# aircat.net
KiCad netlist of a schematic drawn in EAGLE
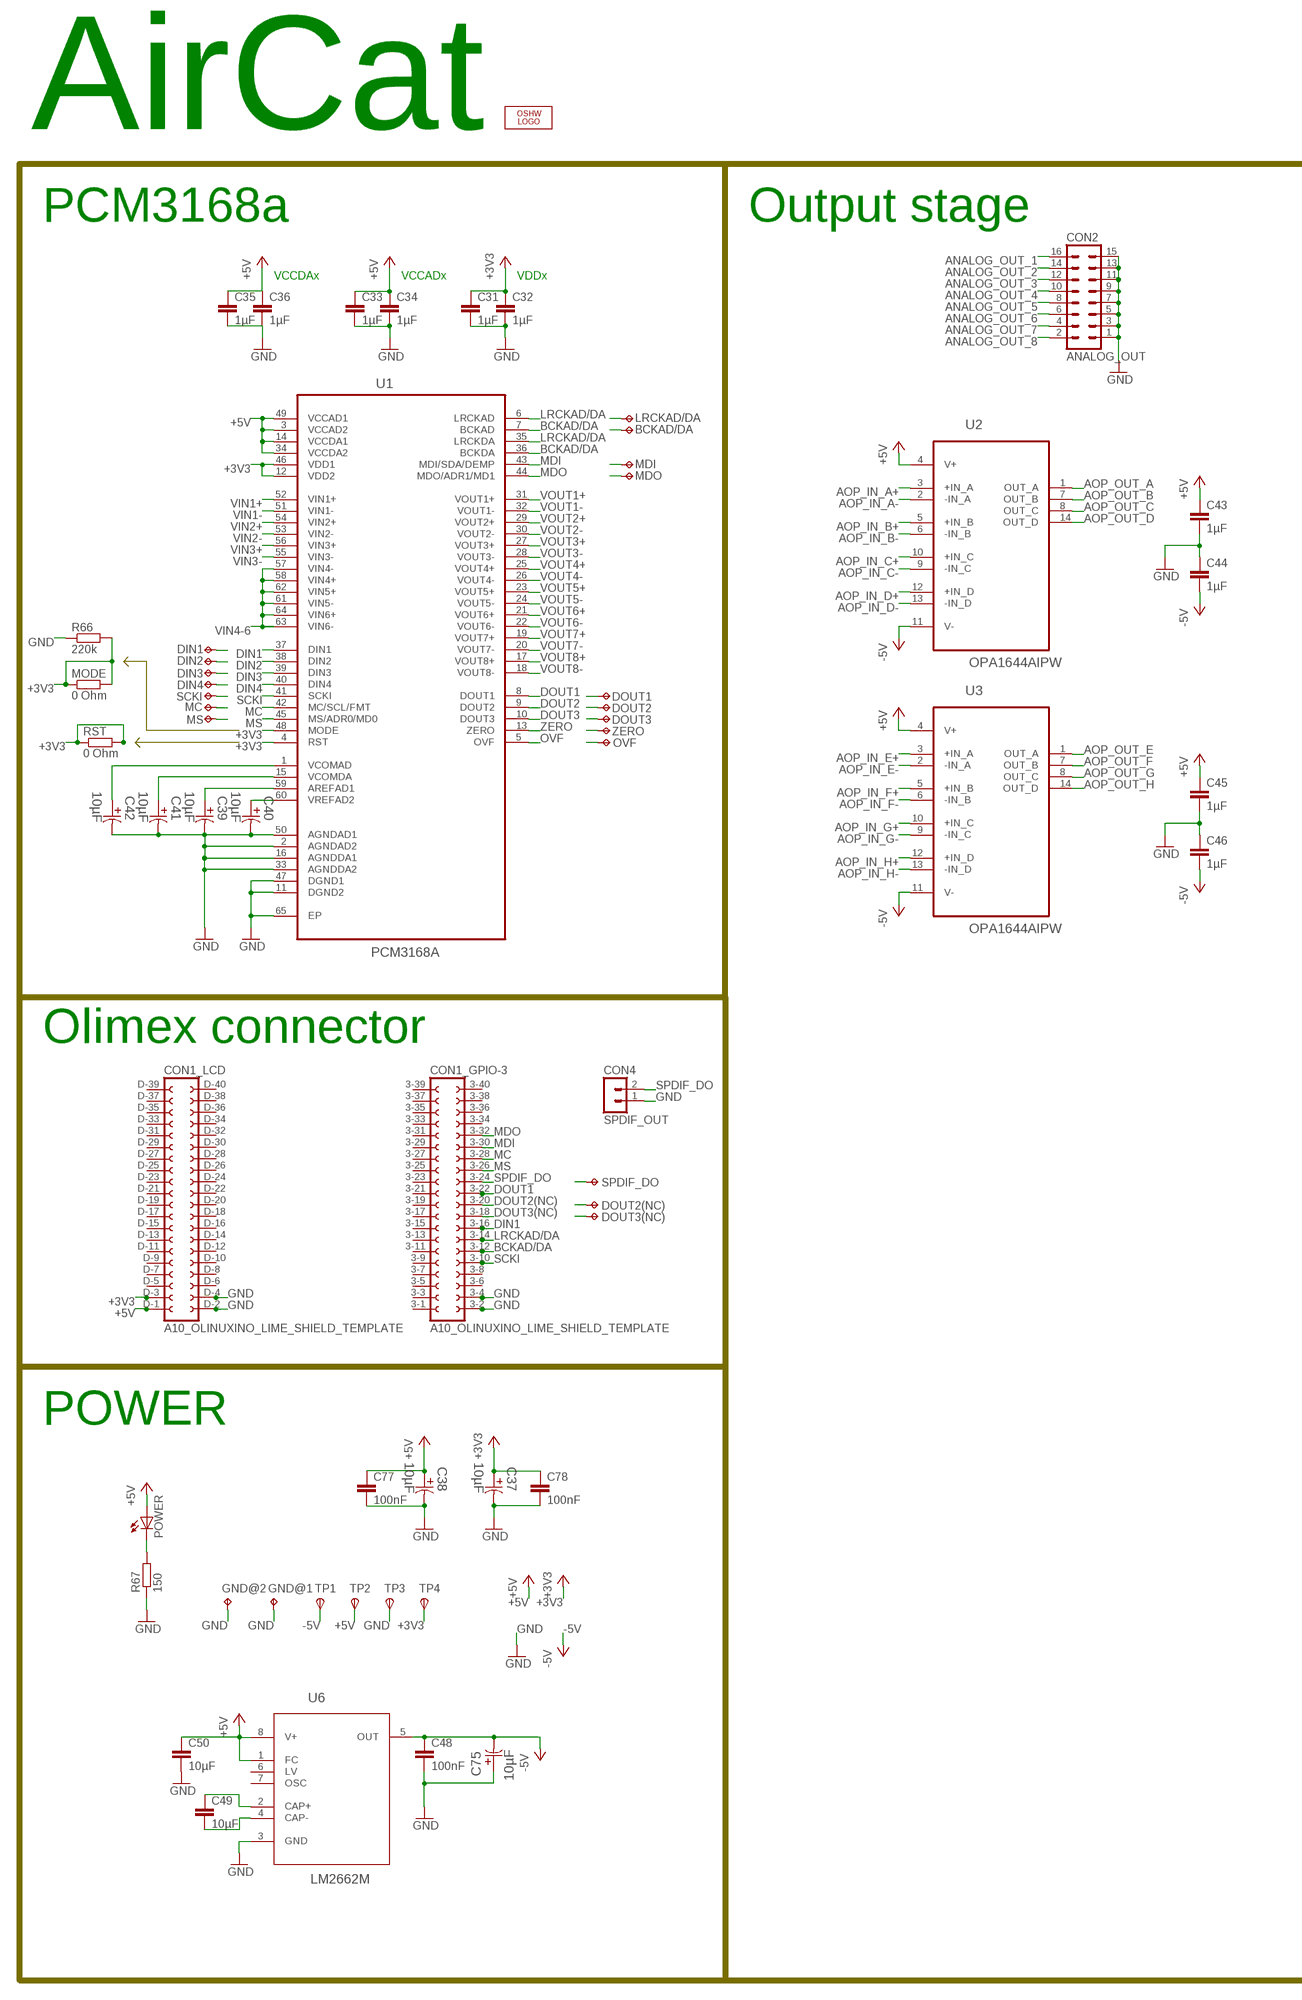
[diagram p0: schematic, sheet 1, part 1 of 2]
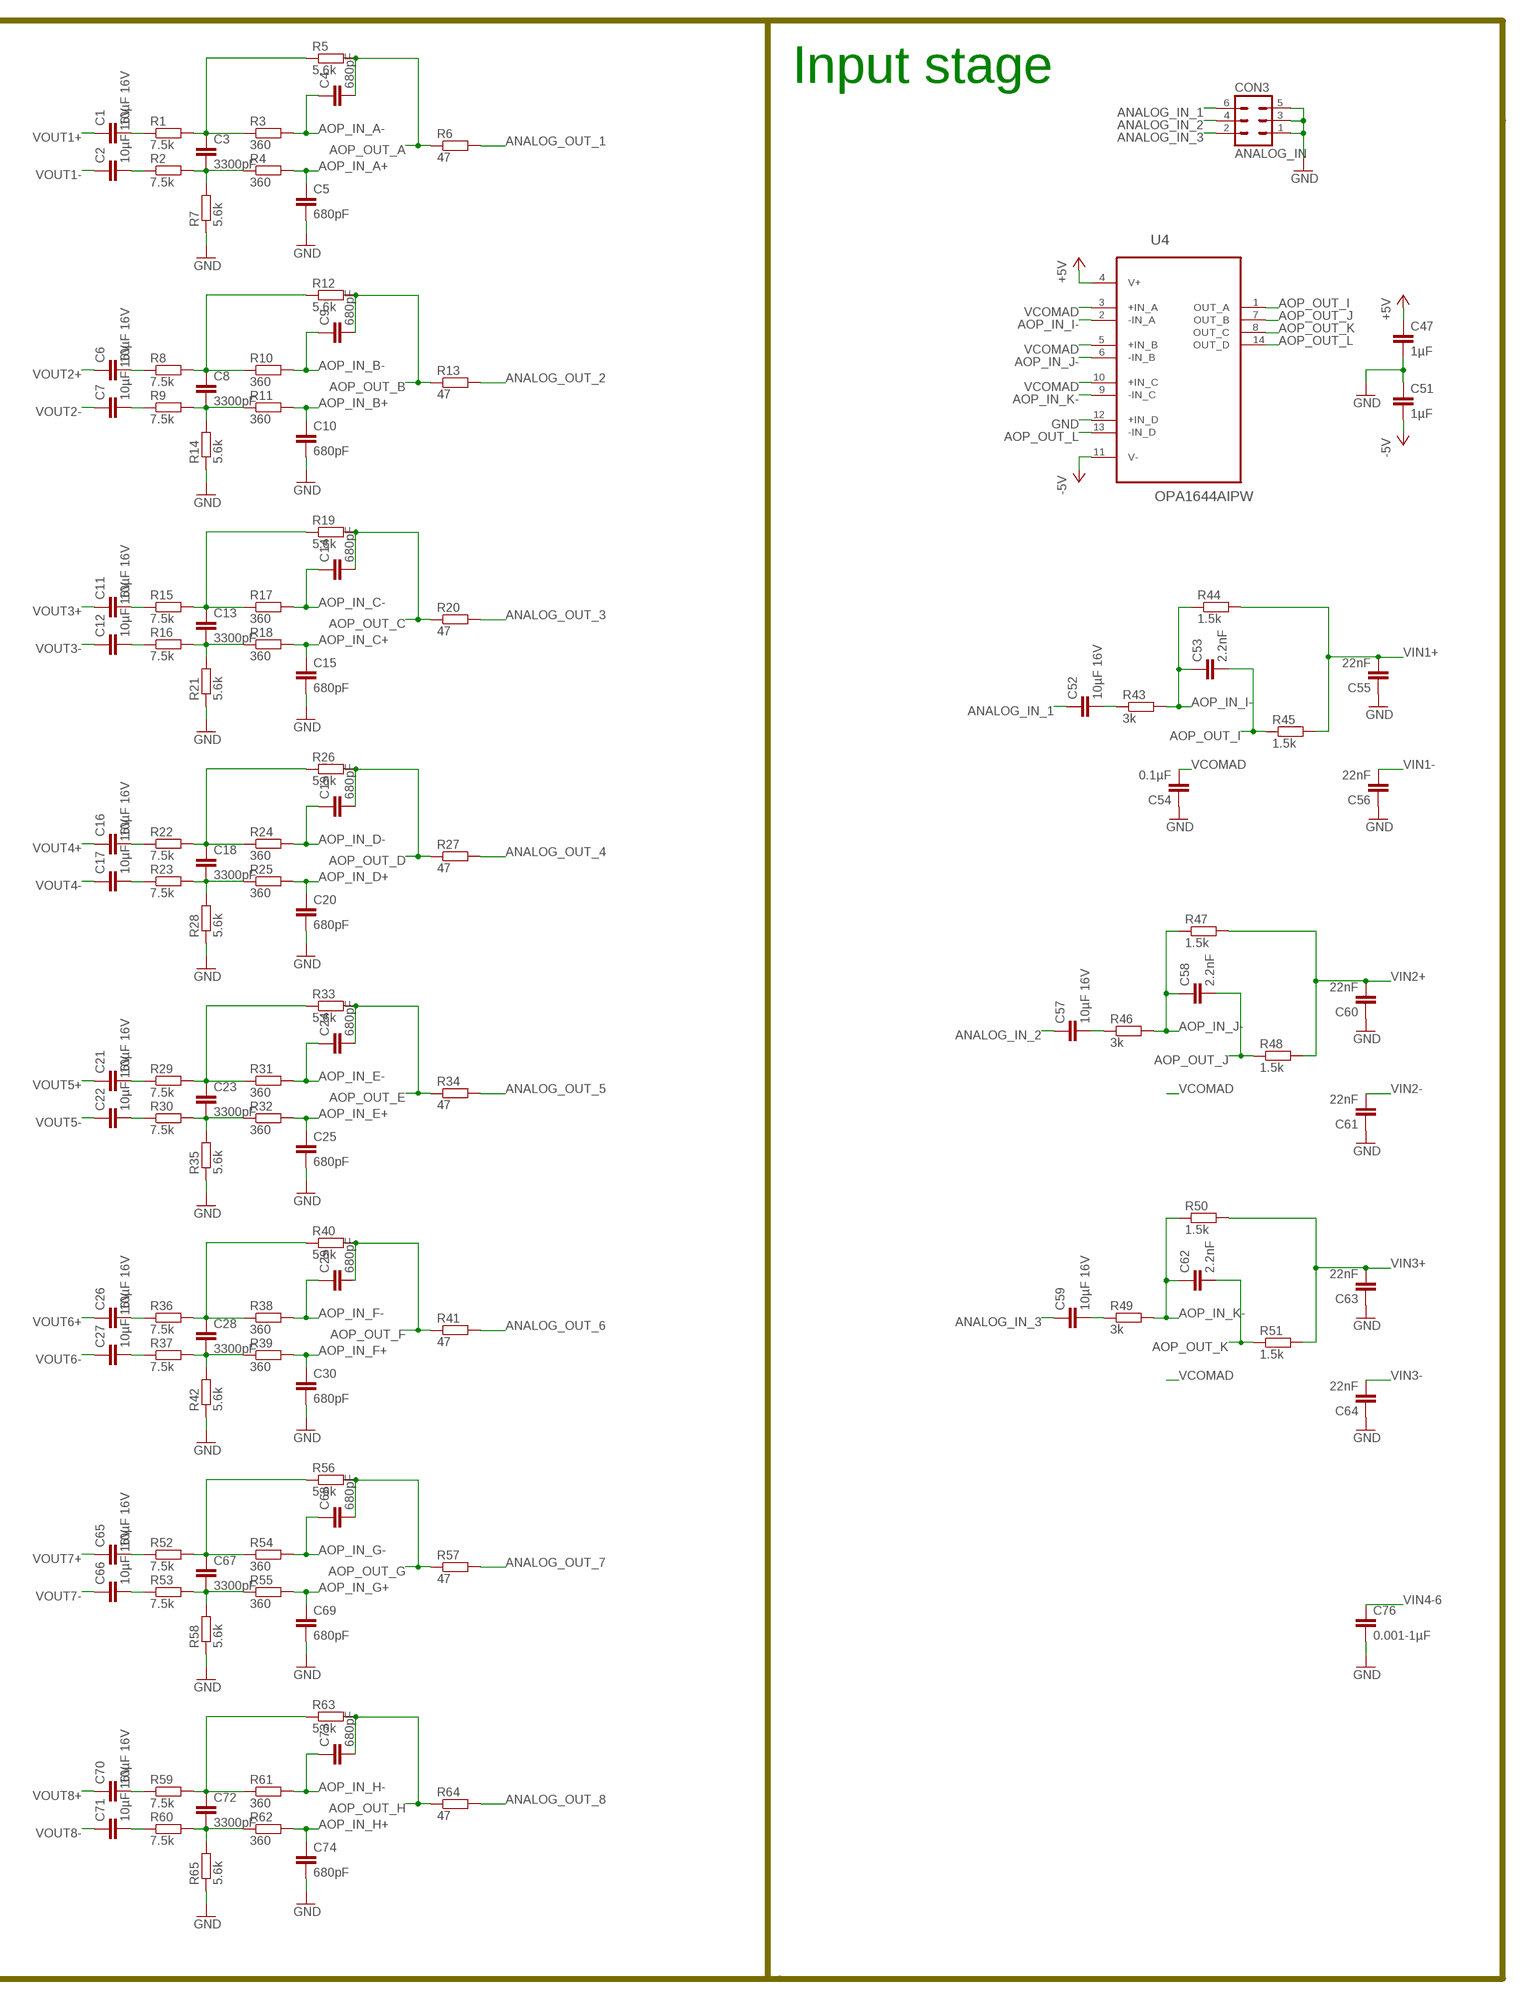
[diagram p1: schematic, sheet 1, part 2 of 2]

(export (version "E")
  (design (tool "Eeschema 10.0.6"))
  (components
    (comp (ref "BCKAD/DA")
      (value "TPTP10SQ")
      (footprint "eagle-import:TP10SQ")
      (libsource (lib "eagle-import") (part "TPTP10SQ"))
    )
    (comp (ref "C1")
      (value "10µF 16V")
      (footprint "eagle-import:C0805")
      (fields (field (name "MF") "AVX") (field (name "MPN") "1206YD106KAT2A"))
      (libsource (lib "eagle-import") (part "C-EUC0805"))
    )
    (comp (ref "C2")
      (value "10µF 16V")
      (footprint "eagle-import:C0805")
      (fields (field (name "MF") "AVX") (field (name "MPN") "1206YD106KAT2A"))
      (libsource (lib "eagle-import") (part "C-EUC0805"))
    )
    (comp (ref "C3")
      (value "3300pF")
      (footprint "eagle-import:C0603")
      (fields (field (name "MF") "AVX") (field (name "MPN") "06035C332KAT2A"))
      (libsource (lib "eagle-import") (part "C-EUC0603"))
    )
    (comp (ref "C4")
      (value "680pF")
      (footprint "eagle-import:C0603")
      (fields (field (name "MF") "KEMET") (field (name "MPN") "C0603C681J5GACTU"))
      (libsource (lib "eagle-import") (part "C-EUC0603"))
    )
    (comp (ref "C5")
      (value "680pF")
      (footprint "eagle-import:C0603")
      (fields (field (name "MF") "KEMET") (field (name "MPN") "C0603C681J5GACTU"))
      (libsource (lib "eagle-import") (part "C-EUC0603"))
    )
    (comp (ref "C6")
      (value "10µF 16V")
      (footprint "eagle-import:C0805")
      (fields (field (name "MF") "AVX") (field (name "MPN") "1206YD106KAT2A"))
      (libsource (lib "eagle-import") (part "C-EUC0805"))
    )
    (comp (ref "C7")
      (value "10µF 16V")
      (footprint "eagle-import:C0805")
      (fields (field (name "MF") "AVX") (field (name "MPN") "1206YD106KAT2A"))
      (libsource (lib "eagle-import") (part "C-EUC0805"))
    )
    (comp (ref "C8")
      (value "3300pF")
      (footprint "eagle-import:C0603")
      (fields (field (name "MF") "AVX") (field (name "MPN") "06035C332KAT2A"))
      (libsource (lib "eagle-import") (part "C-EUC0603"))
    )
    (comp (ref "C9")
      (value "680pF")
      (footprint "eagle-import:C0603")
      (fields (field (name "MF") "KEMET") (field (name "MPN") "C0603C681J5GACTU"))
      (libsource (lib "eagle-import") (part "C-EUC0603"))
    )
    (comp (ref "C10")
      (value "680pF")
      (footprint "eagle-import:C0603")
      (fields (field (name "MF") "KEMET") (field (name "MPN") "C0603C681J5GACTU"))
      (libsource (lib "eagle-import") (part "C-EUC0603"))
    )
    (comp (ref "C11")
      (value "10µF 16V")
      (footprint "eagle-import:C0805")
      (fields (field (name "MF") "AVX") (field (name "MPN") "1206YD106KAT2A"))
      (libsource (lib "eagle-import") (part "C-EUC0805"))
    )
    (comp (ref "C12")
      (value "10µF 16V")
      (footprint "eagle-import:C0805")
      (fields (field (name "MF") "AVX") (field (name "MPN") "1206YD106KAT2A"))
      (libsource (lib "eagle-import") (part "C-EUC0805"))
    )
    (comp (ref "C13")
      (value "3300pF")
      (footprint "eagle-import:C0603")
      (fields (field (name "MF") "AVX") (field (name "MPN") "06035C332KAT2A"))
      (libsource (lib "eagle-import") (part "C-EUC0603"))
    )
    (comp (ref "C14")
      (value "680pF")
      (footprint "eagle-import:C0603")
      (fields (field (name "MF") "KEMET") (field (name "MPN") "C0603C681J5GACTU"))
      (libsource (lib "eagle-import") (part "C-EUC0603"))
    )
    (comp (ref "C15")
      (value "680pF")
      (footprint "eagle-import:C0603")
      (fields (field (name "MF") "KEMET") (field (name "MPN") "C0603C681J5GACTU"))
      (libsource (lib "eagle-import") (part "C-EUC0603"))
    )
    (comp (ref "C16")
      (value "10µF 16V")
      (footprint "eagle-import:C0805")
      (fields (field (name "MF") "AVX") (field (name "MPN") "1206YD106KAT2A"))
      (libsource (lib "eagle-import") (part "C-EUC0805"))
    )
    (comp (ref "C17")
      (value "10µF 16V")
      (footprint "eagle-import:C0805")
      (fields (field (name "MF") "AVX") (field (name "MPN") "1206YD106KAT2A"))
      (libsource (lib "eagle-import") (part "C-EUC0805"))
    )
    (comp (ref "C18")
      (value "3300pF")
      (footprint "eagle-import:C0603")
      (fields (field (name "MF") "AVX") (field (name "MPN") "06035C332KAT2A"))
      (libsource (lib "eagle-import") (part "C-EUC0603"))
    )
    (comp (ref "C19")
      (value "680pF")
      (footprint "eagle-import:C0603")
      (fields (field (name "MF") "KEMET") (field (name "MPN") "C0603C681J5GACTU"))
      (libsource (lib "eagle-import") (part "C-EUC0603"))
    )
    (comp (ref "C20")
      (value "680pF")
      (footprint "eagle-import:C0603")
      (fields (field (name "MF") "KEMET") (field (name "MPN") "C0603C681J5GACTU"))
      (libsource (lib "eagle-import") (part "C-EUC0603"))
    )
    (comp (ref "C21")
      (value "10µF 16V")
      (footprint "eagle-import:C0805")
      (fields (field (name "MF") "AVX") (field (name "MPN") "1206YD106KAT2A"))
      (libsource (lib "eagle-import") (part "C-EUC0805"))
    )
    (comp (ref "C22")
      (value "10µF 16V")
      (footprint "eagle-import:C0805")
      (fields (field (name "MF") "AVX") (field (name "MPN") "1206YD106KAT2A"))
      (libsource (lib "eagle-import") (part "C-EUC0805"))
    )
    (comp (ref "C23")
      (value "3300pF")
      (footprint "eagle-import:C0603")
      (fields (field (name "MF") "AVX") (field (name "MPN") "06035C332KAT2A"))
      (libsource (lib "eagle-import") (part "C-EUC0603"))
    )
    (comp (ref "C24")
      (value "680pF")
      (footprint "eagle-import:C0603")
      (fields (field (name "MF") "KEMET") (field (name "MPN") "C0603C681J5GACTU"))
      (libsource (lib "eagle-import") (part "C-EUC0603"))
    )
    (comp (ref "C25")
      (value "680pF")
      (footprint "eagle-import:C0603")
      (fields (field (name "MF") "KEMET") (field (name "MPN") "C0603C681J5GACTU"))
      (libsource (lib "eagle-import") (part "C-EUC0603"))
    )
    (comp (ref "C26")
      (value "10µF 16V")
      (footprint "eagle-import:C0805")
      (fields (field (name "MF") "AVX") (field (name "MPN") "1206YD106KAT2A"))
      (libsource (lib "eagle-import") (part "C-EUC0805"))
    )
    (comp (ref "C27")
      (value "10µF 16V")
      (footprint "eagle-import:C0805")
      (fields (field (name "MF") "AVX") (field (name "MPN") "1206YD106KAT2A"))
      (libsource (lib "eagle-import") (part "C-EUC0805"))
    )
    (comp (ref "C28")
      (value "3300pF")
      (footprint "eagle-import:C0603")
      (fields (field (name "MF") "AVX") (field (name "MPN") "06035C332KAT2A"))
      (libsource (lib "eagle-import") (part "C-EUC0603"))
    )
    (comp (ref "C29")
      (value "680pF")
      (footprint "eagle-import:C0603")
      (fields (field (name "MF") "KEMET") (field (name "MPN") "C0603C681J5GACTU"))
      (libsource (lib "eagle-import") (part "C-EUC0603"))
    )
    (comp (ref "C30")
      (value "680pF")
      (footprint "eagle-import:C0603")
      (fields (field (name "MF") "KEMET") (field (name "MPN") "C0603C681J5GACTU"))
      (libsource (lib "eagle-import") (part "C-EUC0603"))
    )
    (comp (ref "C31")
      (value "1µF")
      (footprint "eagle-import:C0603")
      (fields (field (name "MF") "AVX") (field (name "MPN") "0603ZD105KAT2A"))
      (libsource (lib "eagle-import") (part "C-EUC0603"))
    )
    (comp (ref "C32")
      (value "1µF")
      (footprint "eagle-import:C0603")
      (fields (field (name "MF") "AVX") (field (name "MPN") "0603ZD105KAT2A"))
      (libsource (lib "eagle-import") (part "C-EUC0603"))
    )
    (comp (ref "C33")
      (value "1µF")
      (footprint "eagle-import:C0603")
      (fields (field (name "MF") "AVX") (field (name "MPN") "0603ZD105KAT2A"))
      (libsource (lib "eagle-import") (part "C-EUC0603"))
    )
    (comp (ref "C34")
      (value "1µF")
      (footprint "eagle-import:C0603")
      (fields (field (name "MF") "AVX") (field (name "MPN") "0603ZD105KAT2A"))
      (libsource (lib "eagle-import") (part "C-EUC0603"))
    )
    (comp (ref "C35")
      (value "1µF")
      (footprint "eagle-import:C0603")
      (fields (field (name "MF") "AVX") (field (name "MPN") "0603ZD105KAT2A"))
      (libsource (lib "eagle-import") (part "C-EUC0603"))
    )
    (comp (ref "C36")
      (value "1µF")
      (footprint "eagle-import:C0603")
      (fields (field (name "MF") "AVX") (field (name "MPN") "0603ZD105KAT2A"))
      (libsource (lib "eagle-import") (part "C-EUC0603"))
    )
    (comp (ref "C37")
      (value "10µF")
      (footprint "eagle-import:CAPAE430X610N")
      (fields
        (field (name "MPN") "EEE-FK1V100UR")
        (field (name "TOLERANCE") "±20 %")
        (field (name "MF") "PANASONIC")
        (field (name "MPN_1") "EEEFK1V100UR")
        (field (name "OC_FARNELL") "9695826")
      )
      (libsource (lib "eagle-import") (part "EEE--CASE-BFK1V100UR"))
    )
    (comp (ref "C38")
      (value "10µF")
      (footprint "eagle-import:CAPAE430X610N")
      (fields
        (field (name "MPN") "EEE-FK1V100UR")
        (field (name "TOLERANCE") "±20 %")
        (field (name "MF") "PANASONIC")
        (field (name "MPN_1") "EEEFK1V100UR")
        (field (name "OC_FARNELL") "9695826")
        (field (name "OC_NEWARK") "96K9406")
        (field (name "PACKAGE") "CASE-B")
        (field (name "SUPPLIER") "PANASONIC")
        (field (name "TOLERANCE_1") "±20 %")
        (field (name "VOLTAGERATING") "35V")
      )
      (libsource (lib "eagle-import") (part "EEE--CASE-BFK1V100UR"))
    )
    (comp (ref "C39")
      (value "10µF")
      (footprint "eagle-import:CAPAE430X610N")
      (fields
        (field (name "MPN") "EEE-FK1V100UR")
        (field (name "TOLERANCE") "±20 %")
        (field (name "MF") "PANASONIC")
        (field (name "MPN_1") "EEEFK1V100UR")
        (field (name "OC_FARNELL") "9695826")
        (field (name "OC_NEWARK") "96K9406")
        (field (name "PACKAGE") "CASE-B")
        (field (name "SUPPLIER") "PANASONIC")
        (field (name "TOLERANCE_1") "±20 %")
        (field (name "VOLTAGERATING") "35V")
      )
      (libsource (lib "eagle-import") (part "EEE--CASE-BFK1V100UR"))
    )
    (comp (ref "C40")
      (value "10µF")
      (footprint "eagle-import:CAPAE430X610N")
      (fields
        (field (name "MPN") "EEE-FK1V100UR")
        (field (name "TOLERANCE") "±20 %")
        (field (name "MF") "PANASONIC")
        (field (name "MPN_1") "EEEFK1V100UR")
        (field (name "OC_FARNELL") "9695826")
        (field (name "OC_NEWARK") "96K9406")
        (field (name "PACKAGE") "CASE-B")
        (field (name "SUPPLIER") "PANASONIC")
        (field (name "TOLERANCE_1") "±20 %")
        (field (name "VOLTAGERATING") "35V")
      )
      (libsource (lib "eagle-import") (part "EEE--CASE-BFK1V100UR"))
    )
    (comp (ref "C41")
      (value "10µF")
      (footprint "eagle-import:CAPAE430X610N")
      (fields
        (field (name "MPN") "EEE-FK1V100UR")
        (field (name "TOLERANCE") "±20 %")
        (field (name "MF") "PANASONIC")
        (field (name "MPN_1") "EEEFK1V100UR")
        (field (name "OC_FARNELL") "9695826")
        (field (name "OC_NEWARK") "96K9406")
        (field (name "PACKAGE") "CASE-B")
        (field (name "SUPPLIER") "PANASONIC")
        (field (name "TOLERANCE_1") "±20 %")
        (field (name "VOLTAGERATING") "35V")
      )
      (libsource (lib "eagle-import") (part "EEE--CASE-BFK1V100UR"))
    )
    (comp (ref "C42")
      (value "10µF")
      (footprint "eagle-import:CAPAE430X610N")
      (fields
        (field (name "MPN") "EEE-FK1V100UR")
        (field (name "TOLERANCE") "±20 %")
        (field (name "MF") "PANASONIC")
        (field (name "MPN_1") "EEEFK1V100UR")
        (field (name "OC_FARNELL") "9695826")
        (field (name "OC_NEWARK") "96K9406")
        (field (name "PACKAGE") "CASE-B")
        (field (name "SUPPLIER") "PANASONIC")
        (field (name "TOLERANCE_1") "±20 %")
        (field (name "VOLTAGERATING") "35V")
      )
      (libsource (lib "eagle-import") (part "EEE--CASE-BFK1V100UR"))
    )
    (comp (ref "C43")
      (value "1µF")
      (footprint "eagle-import:C0603")
      (fields (field (name "MF") "AVX") (field (name "MPN") "0603ZD105KAT2A"))
      (libsource (lib "eagle-import") (part "C-EUC0603"))
    )
    (comp (ref "C44")
      (value "1µF")
      (footprint "eagle-import:C0603")
      (fields (field (name "MF") "AVX") (field (name "MPN") "0603ZD105KAT2A"))
      (libsource (lib "eagle-import") (part "C-EUC0603"))
    )
    (comp (ref "C45")
      (value "1µF")
      (footprint "eagle-import:C0603")
      (fields (field (name "MF") "AVX") (field (name "MPN") "0603ZD105KAT2A"))
      (libsource (lib "eagle-import") (part "C-EUC0603"))
    )
    (comp (ref "C46")
      (value "1µF")
      (footprint "eagle-import:C0603")
      (fields (field (name "MF") "AVX") (field (name "MPN") "0603ZD105KAT2A"))
      (libsource (lib "eagle-import") (part "C-EUC0603"))
    )
    (comp (ref "C47")
      (value "1µF")
      (footprint "eagle-import:C0603")
      (fields (field (name "MF") "AVX") (field (name "MPN") "0603ZD105KAT2A"))
      (libsource (lib "eagle-import") (part "C-EUC0603"))
    )
    (comp (ref "C48")
      (value "100nF")
      (footprint "eagle-import:C0603")
      (fields (field (name "MF") "SANYO") (field (name "MPN") "10SVP10M"))
      (libsource (lib "eagle-import") (part "C-EUC0603"))
    )
    (comp (ref "C49")
      (value "10µF")
      (footprint "eagle-import:C0805")
      (fields (field (name "MF") "SANYO") (field (name "MPN") "10SVP10M"))
      (libsource (lib "eagle-import") (part "C-EUC0805"))
    )
    (comp (ref "C50")
      (value "10µF")
      (footprint "eagle-import:C0805")
      (fields (field (name "MF") "SANYO") (field (name "MPN") "10SVP10M"))
      (libsource (lib "eagle-import") (part "C-EUC0805"))
    )
    (comp (ref "C51")
      (value "1µF")
      (footprint "eagle-import:C0603")
      (fields (field (name "MF") "AVX") (field (name "MPN") "0603ZD105KAT2A"))
      (libsource (lib "eagle-import") (part "C-EUC0603"))
    )
    (comp (ref "C52")
      (value "10µF 16V")
      (footprint "eagle-import:C0805")
      (fields (field (name "MF") "AVX") (field (name "MPN") "1206YD106KAT2A"))
      (libsource (lib "eagle-import") (part "C-EUC0805"))
    )
    (comp (ref "C53")
      (value "2.2nF")
      (footprint "eagle-import:C0603")
      (fields (field (name "MF") "AVX") (field (name "MPN") "06035C222KAT2A"))
      (libsource (lib "eagle-import") (part "C-EUC0603"))
    )
    (comp (ref "C54")
      (value "0.1µF")
      (footprint "eagle-import:C0603")
      (fields (field (name "MF") "AVX") (field (name "MPN") "0402YD104KAT2A"))
      (libsource (lib "eagle-import") (part "C-EUC0603"))
    )
    (comp (ref "C55")
      (value "22nF")
      (footprint "eagle-import:C0603")
      (fields (field (name "MF") "AVX") (field (name "MPN") "06033C223KAT2A"))
      (libsource (lib "eagle-import") (part "C-EUC0603"))
    )
    (comp (ref "C56")
      (value "22nF")
      (footprint "eagle-import:C0603")
      (fields (field (name "MF") "AVX") (field (name "MPN") "06033C223KAT2A"))
      (libsource (lib "eagle-import") (part "C-EUC0603"))
    )
    (comp (ref "C57")
      (value "10µF 16V")
      (footprint "eagle-import:C0805")
      (fields (field (name "MF") "AVX") (field (name "MPN") "1206YD106KAT2A"))
      (libsource (lib "eagle-import") (part "C-EUC0805"))
    )
    (comp (ref "C58")
      (value "2.2nF")
      (footprint "eagle-import:C0603")
      (fields (field (name "MF") "AVX") (field (name "MPN") "06035C222KAT2A"))
      (libsource (lib "eagle-import") (part "C-EUC0603"))
    )
    (comp (ref "C59")
      (value "10µF 16V")
      (footprint "eagle-import:C0805")
      (fields (field (name "MF") "AVX") (field (name "MPN") "1206YD106KAT2A"))
      (libsource (lib "eagle-import") (part "C-EUC0805"))
    )
    (comp (ref "C60")
      (value "22nF")
      (footprint "eagle-import:C0603")
      (fields (field (name "MF") "AVX") (field (name "MPN") "06033C223KAT2A"))
      (libsource (lib "eagle-import") (part "C-EUC0603"))
    )
    (comp (ref "C61")
      (value "22nF")
      (footprint "eagle-import:C0603")
      (fields (field (name "MF") "AVX") (field (name "MPN") "06033C223KAT2A"))
      (libsource (lib "eagle-import") (part "C-EUC0603"))
    )
    (comp (ref "C62")
      (value "2.2nF")
      (footprint "eagle-import:C0603")
      (fields (field (name "MF") "AVX") (field (name "MPN") "06035C222KAT2A"))
      (libsource (lib "eagle-import") (part "C-EUC0603"))
    )
    (comp (ref "C63")
      (value "22nF")
      (footprint "eagle-import:C0603")
      (fields (field (name "MF") "AVX") (field (name "MPN") "06033C223KAT2A"))
      (libsource (lib "eagle-import") (part "C-EUC0603"))
    )
    (comp (ref "C64")
      (value "22nF")
      (footprint "eagle-import:C0603")
      (fields (field (name "MF") "AVX") (field (name "MPN") "06033C223KAT2A"))
      (libsource (lib "eagle-import") (part "C-EUC0603"))
    )
    (comp (ref "C65")
      (value "10µF 16V")
      (footprint "eagle-import:C0805")
      (fields (field (name "MF") "AVX") (field (name "MPN") "1206YD106KAT2A"))
      (libsource (lib "eagle-import") (part "C-EUC0805"))
    )
    (comp (ref "C66")
      (value "10µF 16V")
      (footprint "eagle-import:C0805")
      (fields (field (name "MF") "AVX") (field (name "MPN") "1206YD106KAT2A"))
      (libsource (lib "eagle-import") (part "C-EUC0805"))
    )
    (comp (ref "C67")
      (value "3300pF")
      (footprint "eagle-import:C0603")
      (fields (field (name "MF") "AVX") (field (name "MPN") "06035C332KAT2A"))
      (libsource (lib "eagle-import") (part "C-EUC0603"))
    )
    (comp (ref "C68")
      (value "680pF")
      (footprint "eagle-import:C0603")
      (fields (field (name "MF") "KEMET") (field (name "MPN") "C0603C681J5GACTU"))
      (libsource (lib "eagle-import") (part "C-EUC0603"))
    )
    (comp (ref "C69")
      (value "680pF")
      (footprint "eagle-import:C0603")
      (fields (field (name "MF") "KEMET") (field (name "MPN") "C0603C681J5GACTU"))
      (libsource (lib "eagle-import") (part "C-EUC0603"))
    )
    (comp (ref "C70")
      (value "10µF 16V")
      (footprint "eagle-import:C0805")
      (fields (field (name "MF") "AVX") (field (name "MPN") "1206YD106KAT2A"))
      (libsource (lib "eagle-import") (part "C-EUC0805"))
    )
    (comp (ref "C71")
      (value "10µF 16V")
      (footprint "eagle-import:C0805")
      (fields (field (name "MF") "AVX") (field (name "MPN") "1206YD106KAT2A"))
      (libsource (lib "eagle-import") (part "C-EUC0805"))
    )
    (comp (ref "C72")
      (value "3300pF")
      (footprint "eagle-import:C0603")
      (fields (field (name "MF") "AVX") (field (name "MPN") "06035C332KAT2A"))
      (libsource (lib "eagle-import") (part "C-EUC0603"))
    )
    (comp (ref "C73")
      (value "680pF")
      (footprint "eagle-import:C0603")
      (fields (field (name "MF") "KEMET") (field (name "MPN") "C0603C681J5GACTU"))
      (libsource (lib "eagle-import") (part "C-EUC0603"))
    )
    (comp (ref "C74")
      (value "680pF")
      (footprint "eagle-import:C0603")
      (fields (field (name "MF") "KEMET") (field (name "MPN") "C0603C681J5GACTU"))
      (libsource (lib "eagle-import") (part "C-EUC0603"))
    )
    (comp (ref "C75")
      (value "10µF")
      (footprint "eagle-import:CAPAE430X610N")
      (fields
        (field (name "MPN") "EEE-FK1V100UR")
        (field (name "TOLERANCE") "±20 %")
        (field (name "MF") "PANASONIC")
        (field (name "MPN_1") "EEEFK1V100UR")
        (field (name "OC_FARNELL") "9695826")
        (field (name "OC_NEWARK") "96K9406")
        (field (name "PACKAGE") "CASE-B")
        (field (name "SUPPLIER") "PANASONIC")
        (field (name "TOLERANCE_1") "±20 %")
        (field (name "VOLTAGERATING") "35V")
      )
      (libsource (lib "eagle-import") (part "EEE--CASE-BFK1V100UR"))
    )
    (comp (ref "C76")
      (value "0.001-1µF")
      (footprint "eagle-import:C0603")
      (libsource (lib "eagle-import") (part "C-EUC0603"))
    )
    (comp (ref "C77")
      (value "100nF")
      (footprint "eagle-import:C0603")
      (fields (field (name "MF") "AVX") (field (name "MPN") "06033D104KAT2A"))
      (libsource (lib "eagle-import") (part "C-EUC0603"))
    )
    (comp (ref "C78")
      (value "100nF")
      (footprint "eagle-import:C0603")
      (fields (field (name "MF") "AVX") (field (name "MPN") "06033D104KAT2A"))
      (libsource (lib "eagle-import") (part "C-EUC0603"))
    )
    (comp (ref "CON1")
      (value "A10_OLINUXINO_LIME_SHIELD_TEMPLATE")
      (footprint "eagle-import:A10_OLINUXINO_LIME_SHIELD")
      (fields (field (name "OC_FARNELL") "unknown"))
      (libsource (lib "eagle-import") (part "A10_OLINUXINO_LIME_SHIELD_TEMPLATE"))
    )
    (comp (ref "CON2")
      (value "ANALOG_OUT")
      (footprint "eagle-import:MA08-2")
      (fields (field (name "OC_FARNELL") "unknown"))
      (libsource (lib "eagle-import") (part "MA08-2"))
    )
    (comp (ref "CON3")
      (value "ANALOG_IN")
      (footprint "eagle-import:MA03-2")
      (fields (field (name "OC_FARNELL") "unknown"))
      (libsource (lib "eagle-import") (part "MA03-2"))
    )
    (comp (ref "CON4")
      (value "SPDIF_OUT")
      (footprint "eagle-import:MA02-1")
      (libsource (lib "eagle-import") (part "MA02-1"))
    )
    (comp (ref "DIN1")
      (value "TPTP10SQ")
      (footprint "eagle-import:TP10SQ")
      (libsource (lib "eagle-import") (part "TPTP10SQ"))
    )
    (comp (ref "DIN2")
      (value "TPTP10SQ")
      (footprint "eagle-import:TP10SQ")
      (libsource (lib "eagle-import") (part "TPTP10SQ"))
    )
    (comp (ref "DIN3")
      (value "TPTP10SQ")
      (footprint "eagle-import:TP10SQ")
      (libsource (lib "eagle-import") (part "TPTP10SQ"))
    )
    (comp (ref "DIN4")
      (value "TPTP10SQ")
      (footprint "eagle-import:TP10SQ")
      (libsource (lib "eagle-import") (part "TPTP10SQ"))
    )
    (comp (ref "DOUT1")
      (value "TPTP10SQ")
      (footprint "eagle-import:TP10SQ")
      (libsource (lib "eagle-import") (part "TPTP10SQ"))
    )
    (comp (ref "DOUT2")
      (value "TPTP10SQ")
      (footprint "eagle-import:TP10SQ")
      (libsource (lib "eagle-import") (part "TPTP10SQ"))
    )
    (comp (ref "DOUT2(NC)")
      (value "TPTP10SQ")
      (footprint "eagle-import:TP10SQ")
      (libsource (lib "eagle-import") (part "TPTP10SQ"))
    )
    (comp (ref "DOUT3")
      (value "TPTP10SQ")
      (footprint "eagle-import:TP10SQ")
      (libsource (lib "eagle-import") (part "TPTP10SQ"))
    )
    (comp (ref "DOUT3(NC)")
      (value "TPTP10SQ")
      (footprint "eagle-import:TP10SQ")
      (libsource (lib "eagle-import") (part "TPTP10SQ"))
    )
    (comp (ref "GND@1")
      (value "TPTP10SQ")
      (footprint "eagle-import:TP10SQ")
      (libsource (lib "eagle-import") (part "TPTP10SQ"))
    )
    (comp (ref "GND@2")
      (value "TPTP10SQ")
      (footprint "eagle-import:TP10SQ")
      (libsource (lib "eagle-import") (part "TPTP10SQ"))
    )
    (comp (ref "LOGO1")
      (value "OSHW_LOGO_FILLX0200-NT")
      (footprint "eagle-import:OSHW_FILLX200_NOTEXT")
      (libsource (lib "eagle-import") (part "OSHW_LOGO_FILLX0200-NT"))
    )
    (comp (ref "LRCKAD/DA")
      (value "TPTP10SQ")
      (footprint "eagle-import:TP10SQ")
      (libsource (lib "eagle-import") (part "TPTP10SQ"))
    )
    (comp (ref "MC")
      (value "TPTP10SQ")
      (footprint "eagle-import:TP10SQ")
      (libsource (lib "eagle-import") (part "TPTP10SQ"))
    )
    (comp (ref "MDI")
      (value "TPTP10SQ")
      (footprint "eagle-import:TP10SQ")
      (libsource (lib "eagle-import") (part "TPTP10SQ"))
    )
    (comp (ref "MDO")
      (value "TPTP10SQ")
      (footprint "eagle-import:TP10SQ")
      (libsource (lib "eagle-import") (part "TPTP10SQ"))
    )
    (comp (ref "MODE")
      (value "0 Ohm")
      (footprint "eagle-import:R0603")
      (libsource (lib "eagle-import") (part "R-EU_R0603"))
    )
    (comp (ref "MS")
      (value "TPTP10SQ")
      (footprint "eagle-import:TP10SQ")
      (libsource (lib "eagle-import") (part "TPTP10SQ"))
    )
    (comp (ref "OVF")
      (value "TPTP10SQ")
      (footprint "eagle-import:TP10SQ")
      (libsource (lib "eagle-import") (part "TPTP10SQ"))
    )
    (comp (ref "POWER")
      (value "LEDSML0603")
      (footprint "eagle-import:SML0603")
      (libsource (lib "eagle-import") (part "LEDSML0603"))
    )
    (comp (ref "R1")
      (value "7.5k")
      (footprint "eagle-import:R0603")
      (fields (field (name "MF") "MULTICOMP") (field (name "MPN") "MCRE000161"))
      (libsource (lib "eagle-import") (part "R-EU_R0603"))
    )
    (comp (ref "R2")
      (value "7.5k")
      (footprint "eagle-import:R0603")
      (fields (field (name "MF") "MULTICOMP") (field (name "MPN") "MCRE000161"))
      (libsource (lib "eagle-import") (part "R-EU_R0603"))
    )
    (comp (ref "R3")
      (value "360")
      (footprint "eagle-import:R0603")
      (libsource (lib "eagle-import") (part "R-EU_R0603"))
    )
    (comp (ref "R4")
      (value "360")
      (footprint "eagle-import:R0603")
      (libsource (lib "eagle-import") (part "R-EU_R0603"))
    )
    (comp (ref "R5")
      (value "5.6k")
      (footprint "eagle-import:R0603")
      (fields (field (name "MF") "MULTICOMP") (field (name "MPN") "MCPWR05FTEW5601"))
      (libsource (lib "eagle-import") (part "R-EU_R0603"))
    )
    (comp (ref "R6")
      (value "47")
      (footprint "eagle-import:R0603")
      (libsource (lib "eagle-import") (part "R-EU_R0603"))
    )
    (comp (ref "R7")
      (value "5.6k")
      (footprint "eagle-import:R0603")
      (fields (field (name "MF") "MULTICOMP") (field (name "MPN") "MCPWR05FTEW5601"))
      (libsource (lib "eagle-import") (part "R-EU_R0603"))
    )
    (comp (ref "R8")
      (value "7.5k")
      (footprint "eagle-import:R0603")
      (fields (field (name "MF") "MULTICOMP") (field (name "MPN") "MCRE000161"))
      (libsource (lib "eagle-import") (part "R-EU_R0603"))
    )
    (comp (ref "R9")
      (value "7.5k")
      (footprint "eagle-import:R0603")
      (fields (field (name "MF") "MULTICOMP") (field (name "MPN") "MCRE000161"))
      (libsource (lib "eagle-import") (part "R-EU_R0603"))
    )
    (comp (ref "R10")
      (value "360")
      (footprint "eagle-import:R0603")
      (libsource (lib "eagle-import") (part "R-EU_R0603"))
    )
    (comp (ref "R11")
      (value "360")
      (footprint "eagle-import:R0603")
      (libsource (lib "eagle-import") (part "R-EU_R0603"))
    )
    (comp (ref "R12")
      (value "5.6k")
      (footprint "eagle-import:R0603")
      (fields (field (name "MF") "MULTICOMP") (field (name "MPN") "MCPWR05FTEW5601"))
      (libsource (lib "eagle-import") (part "R-EU_R0603"))
    )
    (comp (ref "R13")
      (value "47")
      (footprint "eagle-import:R0603")
      (libsource (lib "eagle-import") (part "R-EU_R0603"))
    )
    (comp (ref "R14")
      (value "5.6k")
      (footprint "eagle-import:R0603")
      (fields (field (name "MF") "MULTICOMP") (field (name "MPN") "MCPWR05FTEW5601"))
      (libsource (lib "eagle-import") (part "R-EU_R0603"))
    )
    (comp (ref "R15")
      (value "7.5k")
      (footprint "eagle-import:R0603")
      (fields (field (name "MF") "MULTICOMP") (field (name "MPN") "MCRE000161"))
      (libsource (lib "eagle-import") (part "R-EU_R0603"))
    )
    (comp (ref "R16")
      (value "7.5k")
      (footprint "eagle-import:R0603")
      (fields (field (name "MF") "MULTICOMP") (field (name "MPN") "MCRE000161"))
      (libsource (lib "eagle-import") (part "R-EU_R0603"))
    )
    (comp (ref "R17")
      (value "360")
      (footprint "eagle-import:R0603")
      (libsource (lib "eagle-import") (part "R-EU_R0603"))
    )
    (comp (ref "R18")
      (value "360")
      (footprint "eagle-import:R0603")
      (libsource (lib "eagle-import") (part "R-EU_R0603"))
    )
    (comp (ref "R19")
      (value "5.6k")
      (footprint "eagle-import:R0603")
      (fields (field (name "MF") "MULTICOMP") (field (name "MPN") "MCPWR05FTEW5601"))
      (libsource (lib "eagle-import") (part "R-EU_R0603"))
    )
    (comp (ref "R20")
      (value "47")
      (footprint "eagle-import:R0603")
      (libsource (lib "eagle-import") (part "R-EU_R0603"))
    )
    (comp (ref "R21")
      (value "5.6k")
      (footprint "eagle-import:R0603")
      (fields (field (name "MF") "MULTICOMP") (field (name "MPN") "MCPWR05FTEW5601"))
      (libsource (lib "eagle-import") (part "R-EU_R0603"))
    )
    (comp (ref "R22")
      (value "7.5k")
      (footprint "eagle-import:R0603")
      (fields (field (name "MF") "MULTICOMP") (field (name "MPN") "MCRE000161"))
      (libsource (lib "eagle-import") (part "R-EU_R0603"))
    )
    (comp (ref "R23")
      (value "7.5k")
      (footprint "eagle-import:R0603")
      (fields (field (name "MF") "MULTICOMP") (field (name "MPN") "MCRE000161"))
      (libsource (lib "eagle-import") (part "R-EU_R0603"))
    )
    (comp (ref "R24")
      (value "360")
      (footprint "eagle-import:R0603")
      (libsource (lib "eagle-import") (part "R-EU_R0603"))
    )
    (comp (ref "R25")
      (value "360")
      (footprint "eagle-import:R0603")
      (libsource (lib "eagle-import") (part "R-EU_R0603"))
    )
    (comp (ref "R26")
      (value "5.6k")
      (footprint "eagle-import:R0603")
      (fields (field (name "MF") "MULTICOMP") (field (name "MPN") "MCPWR05FTEW5601"))
      (libsource (lib "eagle-import") (part "R-EU_R0603"))
    )
    (comp (ref "R27")
      (value "47")
      (footprint "eagle-import:R0603")
      (libsource (lib "eagle-import") (part "R-EU_R0603"))
    )
    (comp (ref "R28")
      (value "5.6k")
      (footprint "eagle-import:R0603")
      (fields (field (name "MF") "MULTICOMP") (field (name "MPN") "MCPWR05FTEW5601"))
      (libsource (lib "eagle-import") (part "R-EU_R0603"))
    )
    (comp (ref "R29")
      (value "7.5k")
      (footprint "eagle-import:R0603")
      (fields (field (name "MF") "MULTICOMP") (field (name "MPN") "MCRE000161"))
      (libsource (lib "eagle-import") (part "R-EU_R0603"))
    )
    (comp (ref "R30")
      (value "7.5k")
      (footprint "eagle-import:R0603")
      (fields (field (name "MF") "MULTICOMP") (field (name "MPN") "MCRE000161"))
      (libsource (lib "eagle-import") (part "R-EU_R0603"))
    )
    (comp (ref "R31")
      (value "360")
      (footprint "eagle-import:R0603")
      (libsource (lib "eagle-import") (part "R-EU_R0603"))
    )
    (comp (ref "R32")
      (value "360")
      (footprint "eagle-import:R0603")
      (libsource (lib "eagle-import") (part "R-EU_R0603"))
    )
    (comp (ref "R33")
      (value "5.6k")
      (footprint "eagle-import:R0603")
      (fields (field (name "MF") "MULTICOMP") (field (name "MPN") "MCPWR05FTEW5601"))
      (libsource (lib "eagle-import") (part "R-EU_R0603"))
    )
    (comp (ref "R34")
      (value "47")
      (footprint "eagle-import:R0603")
      (libsource (lib "eagle-import") (part "R-EU_R0603"))
    )
    (comp (ref "R35")
      (value "5.6k")
      (footprint "eagle-import:R0603")
      (fields (field (name "MF") "MULTICOMP") (field (name "MPN") "MCPWR05FTEW5601"))
      (libsource (lib "eagle-import") (part "R-EU_R0603"))
    )
    (comp (ref "R36")
      (value "7.5k")
      (footprint "eagle-import:R0603")
      (fields (field (name "MF") "MULTICOMP") (field (name "MPN") "MCRE000161"))
      (libsource (lib "eagle-import") (part "R-EU_R0603"))
    )
    (comp (ref "R37")
      (value "7.5k")
      (footprint "eagle-import:R0603")
      (fields (field (name "MF") "MULTICOMP") (field (name "MPN") "MCRE000161"))
      (libsource (lib "eagle-import") (part "R-EU_R0603"))
    )
    (comp (ref "R38")
      (value "360")
      (footprint "eagle-import:R0603")
      (libsource (lib "eagle-import") (part "R-EU_R0603"))
    )
    (comp (ref "R39")
      (value "360")
      (footprint "eagle-import:R0603")
      (libsource (lib "eagle-import") (part "R-EU_R0603"))
    )
    (comp (ref "R40")
      (value "5.6k")
      (footprint "eagle-import:R0603")
      (fields (field (name "MF") "MULTICOMP") (field (name "MPN") "MCPWR05FTEW5601"))
      (libsource (lib "eagle-import") (part "R-EU_R0603"))
    )
    (comp (ref "R41")
      (value "47")
      (footprint "eagle-import:R0603")
      (libsource (lib "eagle-import") (part "R-EU_R0603"))
    )
    (comp (ref "R42")
      (value "5.6k")
      (footprint "eagle-import:R0603")
      (fields (field (name "MF") "MULTICOMP") (field (name "MPN") "MCPWR05FTEW5601"))
      (libsource (lib "eagle-import") (part "R-EU_R0603"))
    )
    (comp (ref "R43")
      (value "3k")
      (footprint "eagle-import:R0603")
      (fields (field (name "MF") "WERA") (field (name "MPN") "167I 3K TX  9 X 80 MM"))
      (libsource (lib "eagle-import") (part "R-EU_R0603"))
    )
    (comp (ref "R44")
      (value "1.5k")
      (footprint "eagle-import:R0603")
      (libsource (lib "eagle-import") (part "R-EU_R0603"))
    )
    (comp (ref "R45")
      (value "1.5k")
      (footprint "eagle-import:R0603")
      (libsource (lib "eagle-import") (part "R-EU_R0603"))
    )
    (comp (ref "R46")
      (value "3k")
      (footprint "eagle-import:R0603")
      (fields (field (name "MF") "WERA") (field (name "MPN") "167I 3K TX  9 X 80 MM"))
      (libsource (lib "eagle-import") (part "R-EU_R0603"))
    )
    (comp (ref "R47")
      (value "1.5k")
      (footprint "eagle-import:R0603")
      (libsource (lib "eagle-import") (part "R-EU_R0603"))
    )
    (comp (ref "R48")
      (value "1.5k")
      (footprint "eagle-import:R0603")
      (libsource (lib "eagle-import") (part "R-EU_R0603"))
    )
    (comp (ref "R49")
      (value "3k")
      (footprint "eagle-import:R0603")
      (fields (field (name "MF") "WERA") (field (name "MPN") "167I 3K TX  9 X 80 MM"))
      (libsource (lib "eagle-import") (part "R-EU_R0603"))
    )
    (comp (ref "R50")
      (value "1.5k")
      (footprint "eagle-import:R0603")
      (libsource (lib "eagle-import") (part "R-EU_R0603"))
    )
    (comp (ref "R51")
      (value "1.5k")
      (footprint "eagle-import:R0603")
      (libsource (lib "eagle-import") (part "R-EU_R0603"))
    )
    (comp (ref "R52")
      (value "7.5k")
      (footprint "eagle-import:R0603")
      (fields (field (name "MF") "MULTICOMP") (field (name "MPN") "MCRE000161"))
      (libsource (lib "eagle-import") (part "R-EU_R0603"))
    )
    (comp (ref "R53")
      (value "7.5k")
      (footprint "eagle-import:R0603")
      (fields (field (name "MF") "MULTICOMP") (field (name "MPN") "MCRE000161"))
      (libsource (lib "eagle-import") (part "R-EU_R0603"))
    )
    (comp (ref "R54")
      (value "360")
      (footprint "eagle-import:R0603")
      (libsource (lib "eagle-import") (part "R-EU_R0603"))
    )
    (comp (ref "R55")
      (value "360")
      (footprint "eagle-import:R0603")
      (libsource (lib "eagle-import") (part "R-EU_R0603"))
    )
    (comp (ref "R56")
      (value "5.6k")
      (footprint "eagle-import:R0603")
      (fields (field (name "MF") "MULTICOMP") (field (name "MPN") "MCPWR05FTEW5601"))
      (libsource (lib "eagle-import") (part "R-EU_R0603"))
    )
    (comp (ref "R57")
      (value "47")
      (footprint "eagle-import:R0603")
      (libsource (lib "eagle-import") (part "R-EU_R0603"))
    )
    (comp (ref "R58")
      (value "5.6k")
      (footprint "eagle-import:R0603")
      (fields (field (name "MF") "MULTICOMP") (field (name "MPN") "MCPWR05FTEW5601"))
      (libsource (lib "eagle-import") (part "R-EU_R0603"))
    )
    (comp (ref "R59")
      (value "7.5k")
      (footprint "eagle-import:R0603")
      (fields (field (name "MF") "MULTICOMP") (field (name "MPN") "MCRE000161"))
      (libsource (lib "eagle-import") (part "R-EU_R0603"))
    )
    (comp (ref "R60")
      (value "7.5k")
      (footprint "eagle-import:R0603")
      (fields (field (name "MF") "MULTICOMP") (field (name "MPN") "MCRE000161"))
      (libsource (lib "eagle-import") (part "R-EU_R0603"))
    )
    (comp (ref "R61")
      (value "360")
      (footprint "eagle-import:R0603")
      (libsource (lib "eagle-import") (part "R-EU_R0603"))
    )
    (comp (ref "R62")
      (value "360")
      (footprint "eagle-import:R0603")
      (libsource (lib "eagle-import") (part "R-EU_R0603"))
    )
    (comp (ref "R63")
      (value "5.6k")
      (footprint "eagle-import:R0603")
      (fields (field (name "MF") "MULTICOMP") (field (name "MPN") "MCPWR05FTEW5601"))
      (libsource (lib "eagle-import") (part "R-EU_R0603"))
    )
    (comp (ref "R64")
      (value "47")
      (footprint "eagle-import:R0603")
      (libsource (lib "eagle-import") (part "R-EU_R0603"))
    )
    (comp (ref "R65")
      (value "5.6k")
      (footprint "eagle-import:R0603")
      (fields (field (name "MF") "MULTICOMP") (field (name "MPN") "MCPWR05FTEW5601"))
      (libsource (lib "eagle-import") (part "R-EU_R0603"))
    )
    (comp (ref "R66")
      (value "220k")
      (footprint "eagle-import:R0603")
      (libsource (lib "eagle-import") (part "R-EU_R0603"))
    )
    (comp (ref "R67")
      (value "150")
      (footprint "eagle-import:R0603")
      (fields (field (name "MF") "MULTICOMP") (field (name "MPN") "MCRE000161"))
      (libsource (lib "eagle-import") (part "R-EU_R0603"))
    )
    (comp (ref "RST")
      (value "0 Ohm")
      (footprint "eagle-import:R0603")
      (libsource (lib "eagle-import") (part "R-EU_R0603"))
    )
    (comp (ref "SCKI")
      (value "TPTP10SQ")
      (footprint "eagle-import:TP10SQ")
      (libsource (lib "eagle-import") (part "TPTP10SQ"))
    )
    (comp (ref "SPDIF_DO")
      (value "TPTP10SQ")
      (footprint "eagle-import:TP10SQ")
      (libsource (lib "eagle-import") (part "TPTP10SQ"))
    )
    (comp (ref "TP1")
      (value "-5V")
      (footprint "eagle-import:B1,27")
      (libsource (lib "eagle-import") (part "TPSB1,27"))
    )
    (comp (ref "TP2")
      (value "+5V")
      (footprint "eagle-import:B1,27")
      (libsource (lib "eagle-import") (part "TPSB1,27"))
    )
    (comp (ref "TP3")
      (value "GND")
      (footprint "eagle-import:B1,27")
      (libsource (lib "eagle-import") (part "TPSB1,27"))
    )
    (comp (ref "TP4")
      (value "+3V3")
      (footprint "eagle-import:B1,27")
      (libsource (lib "eagle-import") (part "TPSB1,27"))
    )
    (comp (ref "U1")
      (value "PCM3168A")
      (footprint "eagle-import:QFP50P1200X1200X120-65N")
      (fields
        (field (name "MPN") "PCM3168APAP")
        (field (name "MF") "TEXAS INSTRUMENTS")
        (field (name "MPN_1") "PCM3168APAP")
        (field (name "OC_FARNELL") "1689419")
      )
      (libsource (lib "eagle-import") (part "PCM3168APAP"))
    )
    (comp (ref "U2")
      (value "OPA1644AIPW")
      (footprint "eagle-import:SOP65P640X120-14N")
      (fields
        (field (name "MF") "TEXAS INSTRUMENTS")
        (field (name "MPN") "OPA1644AIPW")
        (field (name "OC_FARNELL") "1882283")
      )
      (libsource (lib "eagle-import") (part "OPA1644AIPW"))
    )
    (comp (ref "U3")
      (value "OPA1644AIPW")
      (footprint "eagle-import:SOP65P640X120-14N")
      (fields
        (field (name "MF") "TEXAS INSTRUMENTS")
        (field (name "MPN") "OPA1644AIPW")
        (field (name "OC_FARNELL") "1882283")
      )
      (libsource (lib "eagle-import") (part "OPA1644AIPW"))
    )
    (comp (ref "U4")
      (value "OPA1644AIPW")
      (footprint "eagle-import:SOP65P640X120-14N")
      (fields
        (field (name "MF") "TEXAS INSTRUMENTS")
        (field (name "MPN") "OPA1644AIPW")
        (field (name "OC_FARNELL") "1882283")
      )
      (libsource (lib "eagle-import") (part "OPA1644AIPW"))
    )
    (comp (ref "U6")
      (value "LM2662M")
      (footprint "eagle-import:SOIC127P620X175-8N")
      (fields
        (field (name "MF") "TEXAS INSTRUMENTS")
        (field (name "MPN") "LM2662M")
        (field (name "OC_FARNELL") "9306803")
      )
      (libsource (lib "eagle-import") (part "LM2662M"))
    )
    (comp (ref "ZERO")
      (value "TPTP10SQ")
      (footprint "eagle-import:TP10SQ")
      (libsource (lib "eagle-import") (part "TPTP10SQ"))
    )
  )
  (nets
    (net (code "1") (name "+3V3") (class "Default")
      (node (ref "C31") (pin "1") (pinfunction "1_1") (pintype "passive"))
      (node (ref "C32") (pin "1") (pinfunction "1_1") (pintype "passive"))
      (node (ref "C37") (pin "1") (pinfunction "1_1") (pintype "passive"))
      (node (ref "C78") (pin "1") (pinfunction "1_1") (pintype "passive"))
      (node (ref "CON1") (pin "D-3") (pinfunction "3_D-3") (pintype "passive"))
      (node (ref "MODE") (pin "1") (pinfunction "1_1") (pintype "passive"))
      (node (ref "MODE") (pin "2") (pinfunction "2_2") (pintype "passive"))
      (node (ref "R66") (pin "2") (pinfunction "2_2") (pintype "passive"))
      (node (ref "RST") (pin "1") (pinfunction "1_1") (pintype "passive"))
      (node (ref "RST") (pin "2") (pinfunction "2_2") (pintype "passive"))
      (node (ref "TP4") (pin "TP") (pinfunction "PP_TP") (pintype "input"))
      (node (ref "U1") (pin "12") (pinfunction "VDD2_12") (pintype "power_in"))
      (node (ref "U1") (pin "4") (pinfunction "RST_4") (pintype "input"))
      (node (ref "U1") (pin "46") (pinfunction "VDD1_46") (pintype "power_in"))
      (node (ref "U1") (pin "48") (pinfunction "MODE_48") (pintype "input"))
    )
    (net (code "2") (name "+5V") (class "Default")
      (node (ref "C33") (pin "1") (pinfunction "1_1") (pintype "passive"))
      (node (ref "C34") (pin "1") (pinfunction "1_1") (pintype "passive"))
      (node (ref "C35") (pin "1") (pinfunction "1_1") (pintype "passive"))
      (node (ref "C36") (pin "1") (pinfunction "1_1") (pintype "passive"))
      (node (ref "C38") (pin "1") (pinfunction "1_1") (pintype "passive"))
      (node (ref "C43") (pin "1") (pinfunction "1_1") (pintype "passive"))
      (node (ref "C45") (pin "1") (pinfunction "1_1") (pintype "passive"))
      (node (ref "C47") (pin "1") (pinfunction "1_1") (pintype "passive"))
      (node (ref "C50") (pin "1") (pinfunction "1_1") (pintype "passive"))
      (node (ref "C77") (pin "1") (pinfunction "1_1") (pintype "passive"))
      (node (ref "CON1") (pin "D-1") (pinfunction "1_D-1") (pintype "passive"))
      (node (ref "POWER") (pin "A") (pinfunction "A_A") (pintype "passive"))
      (node (ref "TP2") (pin "TP") (pinfunction "PP_TP") (pintype "input"))
      (node (ref "U1") (pin "14") (pinfunction "VCCDA1_14") (pintype "power_in"))
      (node (ref "U1") (pin "3") (pinfunction "VCCAD2_3") (pintype "power_in"))
      (node (ref "U1") (pin "34") (pinfunction "VCCDA2_34") (pintype "power_in"))
      (node (ref "U1") (pin "49") (pinfunction "VCCAD1_49") (pintype "power_in"))
      (node (ref "U2") (pin "4") (pinfunction "V+_4") (pintype "power_in"))
      (node (ref "U3") (pin "4") (pinfunction "V+_4") (pintype "power_in"))
      (node (ref "U4") (pin "4") (pinfunction "V+_4") (pintype "power_in"))
      (node (ref "U6") (pin "1") (pinfunction "FC_1") (pintype "input"))
      (node (ref "U6") (pin "8") (pinfunction "V+_8") (pintype "power_in"))
    )
    (net (code "3") (name "-5V") (class "Default")
      (node (ref "C44") (pin "2") (pinfunction "2_2") (pintype "passive"))
      (node (ref "C46") (pin "2") (pinfunction "2_2") (pintype "passive"))
      (node (ref "C48") (pin "1") (pinfunction "1_1") (pintype "passive"))
      (node (ref "C51") (pin "2") (pinfunction "2_2") (pintype "passive"))
      (node (ref "C75") (pin "2") (pinfunction "2_2") (pintype "passive"))
      (node (ref "TP1") (pin "TP") (pinfunction "PP_TP") (pintype "input"))
      (node (ref "U2") (pin "11") (pinfunction "V-_11") (pintype "power_in"))
      (node (ref "U3") (pin "11") (pinfunction "V-_11") (pintype "power_in"))
      (node (ref "U4") (pin "11") (pinfunction "V-_11") (pintype "power_in"))
      (node (ref "U6") (pin "5") (pinfunction "OUT_5") (pintype "output"))
    )
    (net (code "4") (name "/ANALOG_IN_1") (class "Default")
      (node (ref "C52") (pin "1") (pinfunction "1_1") (pintype "passive"))
      (node (ref "CON3") (pin "6") (pinfunction "6_6") (pintype "passive"))
    )
    (net (code "5") (name "/ANALOG_IN_2") (class "Default")
      (node (ref "C57") (pin "1") (pinfunction "1_1") (pintype "passive"))
      (node (ref "CON3") (pin "4") (pinfunction "4_4") (pintype "passive"))
    )
    (net (code "6") (name "/ANALOG_IN_3") (class "Default")
      (node (ref "C59") (pin "1") (pinfunction "1_1") (pintype "passive"))
      (node (ref "CON3") (pin "2") (pinfunction "2_2") (pintype "passive"))
    )
    (net (code "7") (name "/ANALOG_OUT_1") (class "Default")
      (node (ref "CON2") (pin "16") (pinfunction "16_16") (pintype "passive"))
      (node (ref "R6") (pin "2") (pinfunction "2_2") (pintype "passive"))
    )
    (net (code "8") (name "/ANALOG_OUT_2") (class "Default")
      (node (ref "CON2") (pin "14") (pinfunction "14_14") (pintype "passive"))
      (node (ref "R13") (pin "2") (pinfunction "2_2") (pintype "passive"))
    )
    (net (code "9") (name "/ANALOG_OUT_3") (class "Default")
      (node (ref "CON2") (pin "12") (pinfunction "12_12") (pintype "passive"))
      (node (ref "R20") (pin "2") (pinfunction "2_2") (pintype "passive"))
    )
    (net (code "10") (name "/ANALOG_OUT_4") (class "Default")
      (node (ref "CON2") (pin "10") (pinfunction "10_10") (pintype "passive"))
      (node (ref "R27") (pin "2") (pinfunction "2_2") (pintype "passive"))
    )
    (net (code "11") (name "/ANALOG_OUT_5") (class "Default")
      (node (ref "CON2") (pin "8") (pinfunction "8_8") (pintype "passive"))
      (node (ref "R34") (pin "2") (pinfunction "2_2") (pintype "passive"))
    )
    (net (code "12") (name "/ANALOG_OUT_6") (class "Default")
      (node (ref "CON2") (pin "6") (pinfunction "6_6") (pintype "passive"))
      (node (ref "R41") (pin "2") (pinfunction "2_2") (pintype "passive"))
    )
    (net (code "13") (name "/ANALOG_OUT_7") (class "Default")
      (node (ref "CON2") (pin "4") (pinfunction "4_4") (pintype "passive"))
      (node (ref "R57") (pin "2") (pinfunction "2_2") (pintype "passive"))
    )
    (net (code "14") (name "/ANALOG_OUT_8") (class "Default")
      (node (ref "CON2") (pin "2") (pinfunction "2_2") (pintype "passive"))
      (node (ref "R64") (pin "2") (pinfunction "2_2") (pintype "passive"))
    )
    (net (code "15") (name "/AOP_IN_A+") (class "Default")
      (node (ref "C5") (pin "1") (pinfunction "1_1") (pintype "passive"))
      (node (ref "R4") (pin "2") (pinfunction "2_2") (pintype "passive"))
      (node (ref "U2") (pin "3") (pinfunction "+IN_A_3") (pintype "input"))
    )
    (net (code "16") (name "/AOP_IN_A-") (class "Default")
      (node (ref "C4") (pin "1") (pinfunction "1_1") (pintype "passive"))
      (node (ref "R3") (pin "2") (pinfunction "2_2") (pintype "passive"))
      (node (ref "U2") (pin "2") (pinfunction "-IN_A_2") (pintype "input"))
    )
    (net (code "17") (name "/AOP_IN_B+") (class "Default")
      (node (ref "C10") (pin "1") (pinfunction "1_1") (pintype "passive"))
      (node (ref "R11") (pin "2") (pinfunction "2_2") (pintype "passive"))
      (node (ref "U2") (pin "5") (pinfunction "+IN_B_5") (pintype "input"))
    )
    (net (code "18") (name "/AOP_IN_B-") (class "Default")
      (node (ref "C9") (pin "1") (pinfunction "1_1") (pintype "passive"))
      (node (ref "R10") (pin "2") (pinfunction "2_2") (pintype "passive"))
      (node (ref "U2") (pin "6") (pinfunction "-IN_B_6") (pintype "input"))
    )
    (net (code "19") (name "/AOP_IN_C+") (class "Default")
      (node (ref "C15") (pin "1") (pinfunction "1_1") (pintype "passive"))
      (node (ref "R18") (pin "2") (pinfunction "2_2") (pintype "passive"))
      (node (ref "U2") (pin "10") (pinfunction "+IN_C_10") (pintype "input"))
    )
    (net (code "20") (name "/AOP_IN_C-") (class "Default")
      (node (ref "C14") (pin "1") (pinfunction "1_1") (pintype "passive"))
      (node (ref "R17") (pin "2") (pinfunction "2_2") (pintype "passive"))
      (node (ref "U2") (pin "9") (pinfunction "-IN_C_9") (pintype "input"))
    )
    (net (code "21") (name "/AOP_IN_D+") (class "Default")
      (node (ref "C20") (pin "1") (pinfunction "1_1") (pintype "passive"))
      (node (ref "R25") (pin "2") (pinfunction "2_2") (pintype "passive"))
      (node (ref "U2") (pin "12") (pinfunction "+IN_D_12") (pintype "input"))
    )
    (net (code "22") (name "/AOP_IN_D-") (class "Default")
      (node (ref "C19") (pin "1") (pinfunction "1_1") (pintype "passive"))
      (node (ref "R24") (pin "2") (pinfunction "2_2") (pintype "passive"))
      (node (ref "U2") (pin "13") (pinfunction "-IN_D_13") (pintype "input"))
    )
    (net (code "23") (name "/AOP_IN_E+") (class "Default")
      (node (ref "C25") (pin "1") (pinfunction "1_1") (pintype "passive"))
      (node (ref "R32") (pin "2") (pinfunction "2_2") (pintype "passive"))
      (node (ref "U3") (pin "3") (pinfunction "+IN_A_3") (pintype "input"))
    )
    (net (code "24") (name "/AOP_IN_E-") (class "Default")
      (node (ref "C24") (pin "1") (pinfunction "1_1") (pintype "passive"))
      (node (ref "R31") (pin "2") (pinfunction "2_2") (pintype "passive"))
      (node (ref "U3") (pin "2") (pinfunction "-IN_A_2") (pintype "input"))
    )
    (net (code "25") (name "/AOP_IN_F+") (class "Default")
      (node (ref "C30") (pin "1") (pinfunction "1_1") (pintype "passive"))
      (node (ref "R39") (pin "2") (pinfunction "2_2") (pintype "passive"))
      (node (ref "U3") (pin "5") (pinfunction "+IN_B_5") (pintype "input"))
    )
    (net (code "26") (name "/AOP_IN_F-") (class "Default")
      (node (ref "C29") (pin "1") (pinfunction "1_1") (pintype "passive"))
      (node (ref "R38") (pin "2") (pinfunction "2_2") (pintype "passive"))
      (node (ref "U3") (pin "6") (pinfunction "-IN_B_6") (pintype "input"))
    )
    (net (code "27") (name "/AOP_IN_G+") (class "Default")
      (node (ref "C69") (pin "1") (pinfunction "1_1") (pintype "passive"))
      (node (ref "R55") (pin "2") (pinfunction "2_2") (pintype "passive"))
      (node (ref "U3") (pin "10") (pinfunction "+IN_C_10") (pintype "input"))
    )
    (net (code "28") (name "/AOP_IN_G-") (class "Default")
      (node (ref "C68") (pin "1") (pinfunction "1_1") (pintype "passive"))
      (node (ref "R54") (pin "2") (pinfunction "2_2") (pintype "passive"))
      (node (ref "U3") (pin "9") (pinfunction "-IN_C_9") (pintype "input"))
    )
    (net (code "29") (name "/AOP_IN_H+") (class "Default")
      (node (ref "C74") (pin "1") (pinfunction "1_1") (pintype "passive"))
      (node (ref "R62") (pin "2") (pinfunction "2_2") (pintype "passive"))
      (node (ref "U3") (pin "12") (pinfunction "+IN_D_12") (pintype "input"))
    )
    (net (code "30") (name "/AOP_IN_H-") (class "Default")
      (node (ref "C73") (pin "1") (pinfunction "1_1") (pintype "passive"))
      (node (ref "R61") (pin "2") (pinfunction "2_2") (pintype "passive"))
      (node (ref "U3") (pin "13") (pinfunction "-IN_D_13") (pintype "input"))
    )
    (net (code "31") (name "/AOP_IN_I-") (class "Default")
      (node (ref "C53") (pin "1") (pinfunction "1_1") (pintype "passive"))
      (node (ref "R43") (pin "2") (pinfunction "2_2") (pintype "passive"))
      (node (ref "R44") (pin "1") (pinfunction "1_1") (pintype "passive"))
      (node (ref "U4") (pin "2") (pinfunction "-IN_A_2") (pintype "input"))
    )
    (net (code "32") (name "/AOP_IN_J-") (class "Default")
      (node (ref "C58") (pin "1") (pinfunction "1_1") (pintype "passive"))
      (node (ref "R46") (pin "2") (pinfunction "2_2") (pintype "passive"))
      (node (ref "R47") (pin "1") (pinfunction "1_1") (pintype "passive"))
      (node (ref "U4") (pin "6") (pinfunction "-IN_B_6") (pintype "input"))
    )
    (net (code "33") (name "/AOP_IN_K-") (class "Default")
      (node (ref "C62") (pin "1") (pinfunction "1_1") (pintype "passive"))
      (node (ref "R49") (pin "2") (pinfunction "2_2") (pintype "passive"))
      (node (ref "R50") (pin "1") (pinfunction "1_1") (pintype "passive"))
      (node (ref "U4") (pin "9") (pinfunction "-IN_C_9") (pintype "input"))
    )
    (net (code "34") (name "/AOP_OUT_A") (class "Default")
      (node (ref "C4") (pin "2") (pinfunction "2_2") (pintype "passive"))
      (node (ref "R5") (pin "2") (pinfunction "2_2") (pintype "passive"))
      (node (ref "R6") (pin "1") (pinfunction "1_1") (pintype "passive"))
      (node (ref "U2") (pin "1") (pinfunction "OUT_A_1") (pintype "output"))
    )
    (net (code "35") (name "/AOP_OUT_B") (class "Default")
      (node (ref "C9") (pin "2") (pinfunction "2_2") (pintype "passive"))
      (node (ref "R12") (pin "2") (pinfunction "2_2") (pintype "passive"))
      (node (ref "R13") (pin "1") (pinfunction "1_1") (pintype "passive"))
      (node (ref "U2") (pin "7") (pinfunction "OUT_B_7") (pintype "output"))
    )
    (net (code "36") (name "/AOP_OUT_C") (class "Default")
      (node (ref "C14") (pin "2") (pinfunction "2_2") (pintype "passive"))
      (node (ref "R19") (pin "2") (pinfunction "2_2") (pintype "passive"))
      (node (ref "R20") (pin "1") (pinfunction "1_1") (pintype "passive"))
      (node (ref "U2") (pin "8") (pinfunction "OUT_C_8") (pintype "output"))
    )
    (net (code "37") (name "/AOP_OUT_D") (class "Default")
      (node (ref "C19") (pin "2") (pinfunction "2_2") (pintype "passive"))
      (node (ref "R26") (pin "2") (pinfunction "2_2") (pintype "passive"))
      (node (ref "R27") (pin "1") (pinfunction "1_1") (pintype "passive"))
      (node (ref "U2") (pin "14") (pinfunction "OUT_D_14") (pintype "output"))
    )
    (net (code "38") (name "/AOP_OUT_E") (class "Default")
      (node (ref "C24") (pin "2") (pinfunction "2_2") (pintype "passive"))
      (node (ref "R33") (pin "2") (pinfunction "2_2") (pintype "passive"))
      (node (ref "R34") (pin "1") (pinfunction "1_1") (pintype "passive"))
      (node (ref "U3") (pin "1") (pinfunction "OUT_A_1") (pintype "output"))
    )
    (net (code "39") (name "/AOP_OUT_F") (class "Default")
      (node (ref "C29") (pin "2") (pinfunction "2_2") (pintype "passive"))
      (node (ref "R40") (pin "2") (pinfunction "2_2") (pintype "passive"))
      (node (ref "R41") (pin "1") (pinfunction "1_1") (pintype "passive"))
      (node (ref "U3") (pin "7") (pinfunction "OUT_B_7") (pintype "output"))
    )
    (net (code "40") (name "/AOP_OUT_G") (class "Default")
      (node (ref "C68") (pin "2") (pinfunction "2_2") (pintype "passive"))
      (node (ref "R56") (pin "2") (pinfunction "2_2") (pintype "passive"))
      (node (ref "R57") (pin "1") (pinfunction "1_1") (pintype "passive"))
      (node (ref "U3") (pin "8") (pinfunction "OUT_C_8") (pintype "output"))
    )
    (net (code "41") (name "/AOP_OUT_H") (class "Default")
      (node (ref "C73") (pin "2") (pinfunction "2_2") (pintype "passive"))
      (node (ref "R63") (pin "2") (pinfunction "2_2") (pintype "passive"))
      (node (ref "R64") (pin "1") (pinfunction "1_1") (pintype "passive"))
      (node (ref "U3") (pin "14") (pinfunction "OUT_D_14") (pintype "output"))
    )
    (net (code "42") (name "/AOP_OUT_I") (class "Default")
      (node (ref "C53") (pin "2") (pinfunction "2_2") (pintype "passive"))
      (node (ref "R45") (pin "1") (pinfunction "1_1") (pintype "passive"))
      (node (ref "U4") (pin "1") (pinfunction "OUT_A_1") (pintype "output"))
    )
    (net (code "43") (name "/AOP_OUT_J") (class "Default")
      (node (ref "C58") (pin "2") (pinfunction "2_2") (pintype "passive"))
      (node (ref "R48") (pin "1") (pinfunction "1_1") (pintype "passive"))
      (node (ref "U4") (pin "7") (pinfunction "OUT_B_7") (pintype "output"))
    )
    (net (code "44") (name "/AOP_OUT_K") (class "Default")
      (node (ref "C62") (pin "2") (pinfunction "2_2") (pintype "passive"))
      (node (ref "R51") (pin "1") (pinfunction "1_1") (pintype "passive"))
      (node (ref "U4") (pin "8") (pinfunction "OUT_C_8") (pintype "output"))
    )
    (net (code "45") (name "/AOP_OUT_L") (class "Default")
      (node (ref "U4") (pin "13") (pinfunction "-IN_D_13") (pintype "input"))
      (node (ref "U4") (pin "14") (pinfunction "OUT_D_14") (pintype "output"))
    )
    (net (code "46") (name "/BCKAD{slash}DA") (class "Default")
      (node (ref "BCKAD/DA") (pin "TP") (pinfunction "TP_TP") (pintype "input"))
      (node (ref "CON1") (pin "3-12") (pinfunction "12_3-12") (pintype "passive"))
      (node (ref "U1") (pin "36") (pinfunction "BCKDA_36") (pintype "bidirectional"))
      (node (ref "U1") (pin "7") (pinfunction "BCKAD_7") (pintype "bidirectional"))
    )
    (net (code "47") (name "/DIN1") (class "Default")
      (node (ref "CON1") (pin "3-16") (pinfunction "16_3-16") (pintype "passive"))
      (node (ref "DIN1") (pin "TP") (pinfunction "TP_TP") (pintype "input"))
      (node (ref "U1") (pin "37") (pinfunction "DIN1_37") (pintype "input"))
    )
    (net (code "48") (name "/DIN2") (class "Default")
      (node (ref "DIN2") (pin "TP") (pinfunction "TP_TP") (pintype "input"))
      (node (ref "U1") (pin "38") (pinfunction "DIN2_38") (pintype "input"))
    )
    (net (code "49") (name "/DIN3") (class "Default")
      (node (ref "DIN3") (pin "TP") (pinfunction "TP_TP") (pintype "input"))
      (node (ref "U1") (pin "39") (pinfunction "DIN3_39") (pintype "input"))
    )
    (net (code "50") (name "/DIN4") (class "Default")
      (node (ref "DIN4") (pin "TP") (pinfunction "TP_TP") (pintype "input"))
      (node (ref "U1") (pin "40") (pinfunction "DIN4_40") (pintype "input"))
    )
    (net (code "51") (name "/DOUT1") (class "Default")
      (node (ref "CON1") (pin "3-22") (pinfunction "22_3-22") (pintype "passive"))
      (node (ref "DOUT1") (pin "TP") (pinfunction "TP_TP") (pintype "input"))
      (node (ref "U1") (pin "8") (pinfunction "DOUT1_8") (pintype "output"))
    )
    (net (code "52") (name "/DOUT2") (class "Default")
      (node (ref "DOUT2") (pin "TP") (pinfunction "TP_TP") (pintype "input"))
      (node (ref "U1") (pin "9") (pinfunction "DOUT2_9") (pintype "output"))
    )
    (net (code "53") (name "/DOUT2(NC)") (class "Default")
      (node (ref "CON1") (pin "3-20") (pinfunction "20_3-20") (pintype "passive"))
      (node (ref "DOUT2(NC)") (pin "TP") (pinfunction "TP_TP") (pintype "input"))
    )
    (net (code "54") (name "/DOUT3") (class "Default")
      (node (ref "DOUT3") (pin "TP") (pinfunction "TP_TP") (pintype "input"))
      (node (ref "U1") (pin "10") (pinfunction "DOUT3_10") (pintype "output"))
    )
    (net (code "55") (name "/DOUT3(NC)") (class "Default")
      (node (ref "CON1") (pin "3-18") (pinfunction "18_3-18") (pintype "passive"))
      (node (ref "DOUT3(NC)") (pin "TP") (pinfunction "TP_TP") (pintype "input"))
    )
    (net (code "56") (name "/LRCKAD{slash}DA") (class "Default")
      (node (ref "CON1") (pin "3-14") (pinfunction "14_3-14") (pintype "passive"))
      (node (ref "LRCKAD/DA") (pin "TP") (pinfunction "TP_TP") (pintype "input"))
      (node (ref "U1") (pin "35") (pinfunction "LRCKDA_35") (pintype "bidirectional"))
      (node (ref "U1") (pin "6") (pinfunction "LRCKAD_6") (pintype "bidirectional"))
    )
    (net (code "57") (name "/MC") (class "Default")
      (node (ref "CON1") (pin "3-28") (pinfunction "28_3-28") (pintype "passive"))
      (node (ref "MC") (pin "TP") (pinfunction "TP_TP") (pintype "input"))
      (node (ref "U1") (pin "42") (pinfunction "MC/SCL/FMT_42") (pintype "input"))
    )
    (net (code "58") (name "/MDI") (class "Default")
      (node (ref "CON1") (pin "3-30") (pinfunction "30_3-30") (pintype "passive"))
      (node (ref "MDI") (pin "TP") (pinfunction "TP_TP") (pintype "input"))
      (node (ref "U1") (pin "43") (pinfunction "MDI/SDA/DEMP_43") (pintype "bidirectional"))
    )
    (net (code "59") (name "/MDO") (class "Default")
      (node (ref "CON1") (pin "3-32") (pinfunction "32_3-32") (pintype "passive"))
      (node (ref "MDO") (pin "TP") (pinfunction "TP_TP") (pintype "input"))
      (node (ref "U1") (pin "44") (pinfunction "MDO/ADR1/MD1_44") (pintype "bidirectional"))
    )
    (net (code "60") (name "/MS") (class "Default")
      (node (ref "CON1") (pin "3-26") (pinfunction "26_3-26") (pintype "passive"))
      (node (ref "MS") (pin "TP") (pinfunction "TP_TP") (pintype "input"))
      (node (ref "U1") (pin "45") (pinfunction "MS/ADR0/MD0_45") (pintype "input"))
    )
    (net (code "61") (name "/OVF") (class "Default")
      (node (ref "OVF") (pin "TP") (pinfunction "TP_TP") (pintype "input"))
      (node (ref "U1") (pin "5") (pinfunction "OVF_5") (pintype "output"))
    )
    (net (code "62") (name "/SCKI") (class "Default")
      (node (ref "CON1") (pin "3-10") (pinfunction "10_3-10") (pintype "passive"))
      (node (ref "SCKI") (pin "TP") (pinfunction "TP_TP") (pintype "input"))
      (node (ref "U1") (pin "41") (pinfunction "SCKI_41") (pintype "input"))
    )
    (net (code "63") (name "/SPDIF_DO") (class "Default")
      (node (ref "CON1") (pin "3-24") (pinfunction "24_3-24") (pintype "passive"))
      (node (ref "CON4") (pin "2") (pinfunction "2_2") (pintype "passive"))
      (node (ref "SPDIF_DO") (pin "TP") (pinfunction "TP_TP") (pintype "input"))
    )
    (net (code "64") (name "/VCOMAD") (class "Default")
      (node (ref "C42") (pin "1") (pinfunction "1_1") (pintype "passive"))
      (node (ref "C54") (pin "2") (pinfunction "2_2") (pintype "passive"))
      (node (ref "U1") (pin "1") (pinfunction "VCOMAD_1") (pintype "passive"))
      (node (ref "U4") (pin "10") (pinfunction "+IN_C_10") (pintype "input"))
      (node (ref "U4") (pin "3") (pinfunction "+IN_A_3") (pintype "input"))
      (node (ref "U4") (pin "5") (pinfunction "+IN_B_5") (pintype "input"))
    )
    (net (code "65") (name "/VIN1+") (class "Default")
      (node (ref "C55") (pin "2") (pinfunction "2_2") (pintype "passive"))
      (node (ref "R44") (pin "2") (pinfunction "2_2") (pintype "passive"))
      (node (ref "R45") (pin "2") (pinfunction "2_2") (pintype "passive"))
      (node (ref "U1") (pin "52") (pinfunction "VIN1+_52") (pintype "input"))
    )
    (net (code "66") (name "/VIN1-") (class "Default")
      (node (ref "C56") (pin "2") (pinfunction "2_2") (pintype "passive"))
      (node (ref "U1") (pin "51") (pinfunction "VIN1-_51") (pintype "input"))
    )
    (net (code "67") (name "/VIN2+") (class "Default")
      (node (ref "C60") (pin "2") (pinfunction "2_2") (pintype "passive"))
      (node (ref "R47") (pin "2") (pinfunction "2_2") (pintype "passive"))
      (node (ref "R48") (pin "2") (pinfunction "2_2") (pintype "passive"))
      (node (ref "U1") (pin "54") (pinfunction "VIN2+_54") (pintype "input"))
    )
    (net (code "68") (name "/VIN2-") (class "Default")
      (node (ref "C61") (pin "2") (pinfunction "2_2") (pintype "passive"))
      (node (ref "U1") (pin "53") (pinfunction "VIN2-_53") (pintype "input"))
    )
    (net (code "69") (name "/VIN3+") (class "Default")
      (node (ref "C63") (pin "2") (pinfunction "2_2") (pintype "passive"))
      (node (ref "R50") (pin "2") (pinfunction "2_2") (pintype "passive"))
      (node (ref "R51") (pin "2") (pinfunction "2_2") (pintype "passive"))
      (node (ref "U1") (pin "56") (pinfunction "VIN3+_56") (pintype "input"))
    )
    (net (code "70") (name "/VIN3-") (class "Default")
      (node (ref "C64") (pin "2") (pinfunction "2_2") (pintype "passive"))
      (node (ref "U1") (pin "55") (pinfunction "VIN3-_55") (pintype "input"))
    )
    (net (code "71") (name "/VIN4-6") (class "Default")
      (node (ref "C76") (pin "1") (pinfunction "1_1") (pintype "passive"))
      (node (ref "U1") (pin "57") (pinfunction "VIN4-_57") (pintype "input"))
      (node (ref "U1") (pin "58") (pinfunction "VIN4+_58") (pintype "input"))
      (node (ref "U1") (pin "61") (pinfunction "VIN5-_61") (pintype "input"))
      (node (ref "U1") (pin "62") (pinfunction "VIN5+_62") (pintype "input"))
      (node (ref "U1") (pin "63") (pinfunction "VIN6-_63") (pintype "input"))
      (node (ref "U1") (pin "64") (pinfunction "VIN6+_64") (pintype "input"))
    )
    (net (code "72") (name "/VOUT1+") (class "Default")
      (node (ref "C1") (pin "1") (pinfunction "1_1") (pintype "passive"))
      (node (ref "U1") (pin "31") (pinfunction "VOUT1+_31") (pintype "output"))
    )
    (net (code "73") (name "/VOUT1-") (class "Default")
      (node (ref "C2") (pin "1") (pinfunction "1_1") (pintype "passive"))
      (node (ref "U1") (pin "32") (pinfunction "VOUT1-_32") (pintype "output"))
    )
    (net (code "74") (name "/VOUT2+") (class "Default")
      (node (ref "C6") (pin "1") (pinfunction "1_1") (pintype "passive"))
      (node (ref "U1") (pin "29") (pinfunction "VOUT2+_29") (pintype "output"))
    )
    (net (code "75") (name "/VOUT2-") (class "Default")
      (node (ref "C7") (pin "1") (pinfunction "1_1") (pintype "passive"))
      (node (ref "U1") (pin "30") (pinfunction "VOUT2-_30") (pintype "output"))
    )
    (net (code "76") (name "/VOUT3+") (class "Default")
      (node (ref "C11") (pin "1") (pinfunction "1_1") (pintype "passive"))
      (node (ref "U1") (pin "27") (pinfunction "VOUT3+_27") (pintype "output"))
    )
    (net (code "77") (name "/VOUT3-") (class "Default")
      (node (ref "C12") (pin "1") (pinfunction "1_1") (pintype "passive"))
      (node (ref "U1") (pin "28") (pinfunction "VOUT3-_28") (pintype "output"))
    )
    (net (code "78") (name "/VOUT4+") (class "Default")
      (node (ref "C16") (pin "1") (pinfunction "1_1") (pintype "passive"))
      (node (ref "U1") (pin "25") (pinfunction "VOUT4+_25") (pintype "output"))
    )
    (net (code "79") (name "/VOUT4-") (class "Default")
      (node (ref "C17") (pin "1") (pinfunction "1_1") (pintype "passive"))
      (node (ref "U1") (pin "26") (pinfunction "VOUT4-_26") (pintype "output"))
    )
    (net (code "80") (name "/VOUT5+") (class "Default")
      (node (ref "C21") (pin "1") (pinfunction "1_1") (pintype "passive"))
      (node (ref "U1") (pin "23") (pinfunction "VOUT5+_23") (pintype "output"))
    )
    (net (code "81") (name "/VOUT5-") (class "Default")
      (node (ref "C22") (pin "1") (pinfunction "1_1") (pintype "passive"))
      (node (ref "U1") (pin "24") (pinfunction "VOUT5-_24") (pintype "output"))
    )
    (net (code "82") (name "/VOUT6+") (class "Default")
      (node (ref "C26") (pin "1") (pinfunction "1_1") (pintype "passive"))
      (node (ref "U1") (pin "21") (pinfunction "VOUT6+_21") (pintype "output"))
    )
    (net (code "83") (name "/VOUT6-") (class "Default")
      (node (ref "C27") (pin "1") (pinfunction "1_1") (pintype "passive"))
      (node (ref "U1") (pin "22") (pinfunction "VOUT6-_22") (pintype "output"))
    )
    (net (code "84") (name "/VOUT7+") (class "Default")
      (node (ref "C65") (pin "1") (pinfunction "1_1") (pintype "passive"))
      (node (ref "U1") (pin "19") (pinfunction "VOUT7+_19") (pintype "output"))
    )
    (net (code "85") (name "/VOUT7-") (class "Default")
      (node (ref "C66") (pin "1") (pinfunction "1_1") (pintype "passive"))
      (node (ref "U1") (pin "20") (pinfunction "VOUT7-_20") (pintype "output"))
    )
    (net (code "86") (name "/VOUT8+") (class "Default")
      (node (ref "C70") (pin "1") (pinfunction "1_1") (pintype "passive"))
      (node (ref "U1") (pin "17") (pinfunction "VOUT8+_17") (pintype "output"))
    )
    (net (code "87") (name "/VOUT8-") (class "Default")
      (node (ref "C71") (pin "1") (pinfunction "1_1") (pintype "passive"))
      (node (ref "U1") (pin "18") (pinfunction "VOUT8-_18") (pintype "output"))
    )
    (net (code "88") (name "/ZERO") (class "Default")
      (node (ref "U1") (pin "13") (pinfunction "ZERO_13") (pintype "output"))
      (node (ref "ZERO") (pin "TP") (pinfunction "TP_TP") (pintype "input"))
    )
    (net (code "89") (name "GND") (class "Default")
      (node (ref "C10") (pin "2") (pinfunction "2_2") (pintype "passive"))
      (node (ref "C15") (pin "2") (pinfunction "2_2") (pintype "passive"))
      (node (ref "C20") (pin "2") (pinfunction "2_2") (pintype "passive"))
      (node (ref "C25") (pin "2") (pinfunction "2_2") (pintype "passive"))
      (node (ref "C30") (pin "2") (pinfunction "2_2") (pintype "passive"))
      (node (ref "C31") (pin "2") (pinfunction "2_2") (pintype "passive"))
      (node (ref "C32") (pin "2") (pinfunction "2_2") (pintype "passive"))
      (node (ref "C33") (pin "2") (pinfunction "2_2") (pintype "passive"))
      (node (ref "C34") (pin "2") (pinfunction "2_2") (pintype "passive"))
      (node (ref "C35") (pin "2") (pinfunction "2_2") (pintype "passive"))
      (node (ref "C36") (pin "2") (pinfunction "2_2") (pintype "passive"))
      (node (ref "C37") (pin "2") (pinfunction "2_2") (pintype "passive"))
      (node (ref "C38") (pin "2") (pinfunction "2_2") (pintype "passive"))
      (node (ref "C39") (pin "2") (pinfunction "2_2") (pintype "passive"))
      (node (ref "C40") (pin "2") (pinfunction "2_2") (pintype "passive"))
      (node (ref "C41") (pin "2") (pinfunction "2_2") (pintype "passive"))
      (node (ref "C42") (pin "2") (pinfunction "2_2") (pintype "passive"))
      (node (ref "C43") (pin "2") (pinfunction "2_2") (pintype "passive"))
      (node (ref "C44") (pin "1") (pinfunction "1_1") (pintype "passive"))
      (node (ref "C45") (pin "2") (pinfunction "2_2") (pintype "passive"))
      (node (ref "C46") (pin "1") (pinfunction "1_1") (pintype "passive"))
      (node (ref "C47") (pin "2") (pinfunction "2_2") (pintype "passive"))
      (node (ref "C48") (pin "2") (pinfunction "2_2") (pintype "passive"))
      (node (ref "C5") (pin "2") (pinfunction "2_2") (pintype "passive"))
      (node (ref "C50") (pin "2") (pinfunction "2_2") (pintype "passive"))
      (node (ref "C51") (pin "1") (pinfunction "1_1") (pintype "passive"))
      (node (ref "C54") (pin "1") (pinfunction "1_1") (pintype "passive"))
      (node (ref "C55") (pin "1") (pinfunction "1_1") (pintype "passive"))
      (node (ref "C56") (pin "1") (pinfunction "1_1") (pintype "passive"))
      (node (ref "C60") (pin "1") (pinfunction "1_1") (pintype "passive"))
      (node (ref "C61") (pin "1") (pinfunction "1_1") (pintype "passive"))
      (node (ref "C63") (pin "1") (pinfunction "1_1") (pintype "passive"))
      (node (ref "C64") (pin "1") (pinfunction "1_1") (pintype "passive"))
      (node (ref "C69") (pin "2") (pinfunction "2_2") (pintype "passive"))
      (node (ref "C74") (pin "2") (pinfunction "2_2") (pintype "passive"))
      (node (ref "C75") (pin "1") (pinfunction "1_1") (pintype "passive"))
      (node (ref "C76") (pin "2") (pinfunction "2_2") (pintype "passive"))
      (node (ref "C77") (pin "2") (pinfunction "2_2") (pintype "passive"))
      (node (ref "C78") (pin "2") (pinfunction "2_2") (pintype "passive"))
      (node (ref "CON1") (pin "3-2") (pinfunction "2_3-2") (pintype "passive"))
      (node (ref "CON1") (pin "3-4") (pinfunction "4_3-4") (pintype "passive"))
      (node (ref "CON1") (pin "D-2") (pinfunction "2_D-2") (pintype "passive"))
      (node (ref "CON1") (pin "D-4") (pinfunction "4_D-4") (pintype "passive"))
      (node (ref "CON2") (pin "1") (pinfunction "1_1") (pintype "passive"))
      (node (ref "CON2") (pin "11") (pinfunction "11_11") (pintype "passive"))
      (node (ref "CON2") (pin "13") (pinfunction "13_13") (pintype "passive"))
      (node (ref "CON2") (pin "15") (pinfunction "15_15") (pintype "passive"))
      (node (ref "CON2") (pin "3") (pinfunction "3_3") (pintype "passive"))
      (node (ref "CON2") (pin "5") (pinfunction "5_5") (pintype "passive"))
      (node (ref "CON2") (pin "7") (pinfunction "7_7") (pintype "passive"))
      (node (ref "CON2") (pin "9") (pinfunction "9_9") (pintype "passive"))
      (node (ref "CON3") (pin "1") (pinfunction "1_1") (pintype "passive"))
      (node (ref "CON3") (pin "3") (pinfunction "3_3") (pintype "passive"))
      (node (ref "CON3") (pin "5") (pinfunction "5_5") (pintype "passive"))
      (node (ref "CON4") (pin "1") (pinfunction "1_1") (pintype "passive"))
      (node (ref "GND@1") (pin "TP") (pinfunction "TP_TP") (pintype "input"))
      (node (ref "GND@2") (pin "TP") (pinfunction "TP_TP") (pintype "input"))
      (node (ref "R14") (pin "1") (pinfunction "1_1") (pintype "passive"))
      (node (ref "R21") (pin "1") (pinfunction "1_1") (pintype "passive"))
      (node (ref "R28") (pin "1") (pinfunction "1_1") (pintype "passive"))
      (node (ref "R35") (pin "1") (pinfunction "1_1") (pintype "passive"))
      (node (ref "R42") (pin "1") (pinfunction "1_1") (pintype "passive"))
      (node (ref "R58") (pin "1") (pinfunction "1_1") (pintype "passive"))
      (node (ref "R65") (pin "1") (pinfunction "1_1") (pintype "passive"))
      (node (ref "R66") (pin "1") (pinfunction "1_1") (pintype "passive"))
      (node (ref "R67") (pin "1") (pinfunction "1_1") (pintype "passive"))
      (node (ref "R7") (pin "1") (pinfunction "1_1") (pintype "passive"))
      (node (ref "TP3") (pin "TP") (pinfunction "PP_TP") (pintype "input"))
      (node (ref "U1") (pin "11") (pinfunction "DGND2_11") (pintype "passive"))
      (node (ref "U1") (pin "16") (pinfunction "AGNDDA1_16") (pintype "passive"))
      (node (ref "U1") (pin "2") (pinfunction "AGNDAD2_2") (pintype "passive"))
      (node (ref "U1") (pin "33") (pinfunction "AGNDDA2_33") (pintype "passive"))
      (node (ref "U1") (pin "47") (pinfunction "DGND1_47") (pintype "passive"))
      (node (ref "U1") (pin "50") (pinfunction "AGNDAD1_50") (pintype "passive"))
      (node (ref "U1") (pin "65") (pinfunction "EP_65") (pintype "passive"))
      (node (ref "U4") (pin "12") (pinfunction "+IN_D_12") (pintype "input"))
      (node (ref "U6") (pin "3") (pinfunction "GND_3") (pintype "passive"))
    )
    (net (code "90") (name "Net-(C1-Pad2)") (class "Default")
      (node (ref "C1") (pin "2") (pinfunction "2_2") (pintype "passive"))
      (node (ref "R1") (pin "1") (pinfunction "1_1") (pintype "passive"))
    )
    (net (code "91") (name "Net-(C2-Pad2)") (class "Default")
      (node (ref "C2") (pin "2") (pinfunction "2_2") (pintype "passive"))
      (node (ref "R2") (pin "1") (pinfunction "1_1") (pintype "passive"))
    )
    (net (code "92") (name "Net-(C3-Pad1)") (class "Default")
      (node (ref "C3") (pin "1") (pinfunction "1_1") (pintype "passive"))
      (node (ref "R1") (pin "2") (pinfunction "2_2") (pintype "passive"))
      (node (ref "R3") (pin "1") (pinfunction "1_1") (pintype "passive"))
      (node (ref "R5") (pin "1") (pinfunction "1_1") (pintype "passive"))
    )
    (net (code "93") (name "Net-(C3-Pad2)") (class "Default")
      (node (ref "C3") (pin "2") (pinfunction "2_2") (pintype "passive"))
      (node (ref "R2") (pin "2") (pinfunction "2_2") (pintype "passive"))
      (node (ref "R4") (pin "1") (pinfunction "1_1") (pintype "passive"))
      (node (ref "R7") (pin "2") (pinfunction "2_2") (pintype "passive"))
    )
    (net (code "94") (name "Net-(C6-Pad2)") (class "Default")
      (node (ref "C6") (pin "2") (pinfunction "2_2") (pintype "passive"))
      (node (ref "R8") (pin "1") (pinfunction "1_1") (pintype "passive"))
    )
    (net (code "95") (name "Net-(C7-Pad2)") (class "Default")
      (node (ref "C7") (pin "2") (pinfunction "2_2") (pintype "passive"))
      (node (ref "R9") (pin "1") (pinfunction "1_1") (pintype "passive"))
    )
    (net (code "96") (name "Net-(C8-Pad1)") (class "Default")
      (node (ref "C8") (pin "1") (pinfunction "1_1") (pintype "passive"))
      (node (ref "R10") (pin "1") (pinfunction "1_1") (pintype "passive"))
      (node (ref "R12") (pin "1") (pinfunction "1_1") (pintype "passive"))
      (node (ref "R8") (pin "2") (pinfunction "2_2") (pintype "passive"))
    )
    (net (code "97") (name "Net-(C8-Pad2)") (class "Default")
      (node (ref "C8") (pin "2") (pinfunction "2_2") (pintype "passive"))
      (node (ref "R11") (pin "1") (pinfunction "1_1") (pintype "passive"))
      (node (ref "R14") (pin "2") (pinfunction "2_2") (pintype "passive"))
      (node (ref "R9") (pin "2") (pinfunction "2_2") (pintype "passive"))
    )
    (net (code "98") (name "Net-(C11-Pad2)") (class "Default")
      (node (ref "C11") (pin "2") (pinfunction "2_2") (pintype "passive"))
      (node (ref "R15") (pin "1") (pinfunction "1_1") (pintype "passive"))
    )
    (net (code "99") (name "Net-(C12-Pad2)") (class "Default")
      (node (ref "C12") (pin "2") (pinfunction "2_2") (pintype "passive"))
      (node (ref "R16") (pin "1") (pinfunction "1_1") (pintype "passive"))
    )
    (net (code "100") (name "Net-(C13-Pad1)") (class "Default")
      (node (ref "C13") (pin "1") (pinfunction "1_1") (pintype "passive"))
      (node (ref "R15") (pin "2") (pinfunction "2_2") (pintype "passive"))
      (node (ref "R17") (pin "1") (pinfunction "1_1") (pintype "passive"))
      (node (ref "R19") (pin "1") (pinfunction "1_1") (pintype "passive"))
    )
    (net (code "101") (name "Net-(C13-Pad2)") (class "Default")
      (node (ref "C13") (pin "2") (pinfunction "2_2") (pintype "passive"))
      (node (ref "R16") (pin "2") (pinfunction "2_2") (pintype "passive"))
      (node (ref "R18") (pin "1") (pinfunction "1_1") (pintype "passive"))
      (node (ref "R21") (pin "2") (pinfunction "2_2") (pintype "passive"))
    )
    (net (code "102") (name "Net-(C16-Pad2)") (class "Default")
      (node (ref "C16") (pin "2") (pinfunction "2_2") (pintype "passive"))
      (node (ref "R22") (pin "1") (pinfunction "1_1") (pintype "passive"))
    )
    (net (code "103") (name "Net-(C17-Pad2)") (class "Default")
      (node (ref "C17") (pin "2") (pinfunction "2_2") (pintype "passive"))
      (node (ref "R23") (pin "1") (pinfunction "1_1") (pintype "passive"))
    )
    (net (code "104") (name "Net-(C18-Pad1)") (class "Default")
      (node (ref "C18") (pin "1") (pinfunction "1_1") (pintype "passive"))
      (node (ref "R22") (pin "2") (pinfunction "2_2") (pintype "passive"))
      (node (ref "R24") (pin "1") (pinfunction "1_1") (pintype "passive"))
      (node (ref "R26") (pin "1") (pinfunction "1_1") (pintype "passive"))
    )
    (net (code "105") (name "Net-(C18-Pad2)") (class "Default")
      (node (ref "C18") (pin "2") (pinfunction "2_2") (pintype "passive"))
      (node (ref "R23") (pin "2") (pinfunction "2_2") (pintype "passive"))
      (node (ref "R25") (pin "1") (pinfunction "1_1") (pintype "passive"))
      (node (ref "R28") (pin "2") (pinfunction "2_2") (pintype "passive"))
    )
    (net (code "106") (name "Net-(C21-Pad2)") (class "Default")
      (node (ref "C21") (pin "2") (pinfunction "2_2") (pintype "passive"))
      (node (ref "R29") (pin "1") (pinfunction "1_1") (pintype "passive"))
    )
    (net (code "107") (name "Net-(C22-Pad2)") (class "Default")
      (node (ref "C22") (pin "2") (pinfunction "2_2") (pintype "passive"))
      (node (ref "R30") (pin "1") (pinfunction "1_1") (pintype "passive"))
    )
    (net (code "108") (name "Net-(C23-Pad1)") (class "Default")
      (node (ref "C23") (pin "1") (pinfunction "1_1") (pintype "passive"))
      (node (ref "R29") (pin "2") (pinfunction "2_2") (pintype "passive"))
      (node (ref "R31") (pin "1") (pinfunction "1_1") (pintype "passive"))
      (node (ref "R33") (pin "1") (pinfunction "1_1") (pintype "passive"))
    )
    (net (code "109") (name "Net-(C23-Pad2)") (class "Default")
      (node (ref "C23") (pin "2") (pinfunction "2_2") (pintype "passive"))
      (node (ref "R30") (pin "2") (pinfunction "2_2") (pintype "passive"))
      (node (ref "R32") (pin "1") (pinfunction "1_1") (pintype "passive"))
      (node (ref "R35") (pin "2") (pinfunction "2_2") (pintype "passive"))
    )
    (net (code "110") (name "Net-(C26-Pad2)") (class "Default")
      (node (ref "C26") (pin "2") (pinfunction "2_2") (pintype "passive"))
      (node (ref "R36") (pin "1") (pinfunction "1_1") (pintype "passive"))
    )
    (net (code "111") (name "Net-(C27-Pad2)") (class "Default")
      (node (ref "C27") (pin "2") (pinfunction "2_2") (pintype "passive"))
      (node (ref "R37") (pin "1") (pinfunction "1_1") (pintype "passive"))
    )
    (net (code "112") (name "Net-(C28-Pad1)") (class "Default")
      (node (ref "C28") (pin "1") (pinfunction "1_1") (pintype "passive"))
      (node (ref "R36") (pin "2") (pinfunction "2_2") (pintype "passive"))
      (node (ref "R38") (pin "1") (pinfunction "1_1") (pintype "passive"))
      (node (ref "R40") (pin "1") (pinfunction "1_1") (pintype "passive"))
    )
    (net (code "113") (name "Net-(C28-Pad2)") (class "Default")
      (node (ref "C28") (pin "2") (pinfunction "2_2") (pintype "passive"))
      (node (ref "R37") (pin "2") (pinfunction "2_2") (pintype "passive"))
      (node (ref "R39") (pin "1") (pinfunction "1_1") (pintype "passive"))
      (node (ref "R42") (pin "2") (pinfunction "2_2") (pintype "passive"))
    )
    (net (code "114") (name "Net-(C52-Pad2)") (class "Default")
      (node (ref "C52") (pin "2") (pinfunction "2_2") (pintype "passive"))
      (node (ref "R43") (pin "1") (pinfunction "1_1") (pintype "passive"))
    )
    (net (code "115") (name "Net-(C57-Pad2)") (class "Default")
      (node (ref "C57") (pin "2") (pinfunction "2_2") (pintype "passive"))
      (node (ref "R46") (pin "1") (pinfunction "1_1") (pintype "passive"))
    )
    (net (code "116") (name "Net-(C59-Pad2)") (class "Default")
      (node (ref "C59") (pin "2") (pinfunction "2_2") (pintype "passive"))
      (node (ref "R49") (pin "1") (pinfunction "1_1") (pintype "passive"))
    )
    (net (code "117") (name "Net-(C65-Pad2)") (class "Default")
      (node (ref "C65") (pin "2") (pinfunction "2_2") (pintype "passive"))
      (node (ref "R52") (pin "1") (pinfunction "1_1") (pintype "passive"))
    )
    (net (code "118") (name "Net-(C66-Pad2)") (class "Default")
      (node (ref "C66") (pin "2") (pinfunction "2_2") (pintype "passive"))
      (node (ref "R53") (pin "1") (pinfunction "1_1") (pintype "passive"))
    )
    (net (code "119") (name "Net-(C67-Pad1)") (class "Default")
      (node (ref "C67") (pin "1") (pinfunction "1_1") (pintype "passive"))
      (node (ref "R52") (pin "2") (pinfunction "2_2") (pintype "passive"))
      (node (ref "R54") (pin "1") (pinfunction "1_1") (pintype "passive"))
      (node (ref "R56") (pin "1") (pinfunction "1_1") (pintype "passive"))
    )
    (net (code "120") (name "Net-(C67-Pad2)") (class "Default")
      (node (ref "C67") (pin "2") (pinfunction "2_2") (pintype "passive"))
      (node (ref "R53") (pin "2") (pinfunction "2_2") (pintype "passive"))
      (node (ref "R55") (pin "1") (pinfunction "1_1") (pintype "passive"))
      (node (ref "R58") (pin "2") (pinfunction "2_2") (pintype "passive"))
    )
    (net (code "121") (name "Net-(C70-Pad2)") (class "Default")
      (node (ref "C70") (pin "2") (pinfunction "2_2") (pintype "passive"))
      (node (ref "R59") (pin "1") (pinfunction "1_1") (pintype "passive"))
    )
    (net (code "122") (name "Net-(C71-Pad2)") (class "Default")
      (node (ref "C71") (pin "2") (pinfunction "2_2") (pintype "passive"))
      (node (ref "R60") (pin "1") (pinfunction "1_1") (pintype "passive"))
    )
    (net (code "123") (name "Net-(C72-Pad1)") (class "Default")
      (node (ref "C72") (pin "1") (pinfunction "1_1") (pintype "passive"))
      (node (ref "R59") (pin "2") (pinfunction "2_2") (pintype "passive"))
      (node (ref "R61") (pin "1") (pinfunction "1_1") (pintype "passive"))
      (node (ref "R63") (pin "1") (pinfunction "1_1") (pintype "passive"))
    )
    (net (code "124") (name "Net-(C72-Pad2)") (class "Default")
      (node (ref "C72") (pin "2") (pinfunction "2_2") (pintype "passive"))
      (node (ref "R60") (pin "2") (pinfunction "2_2") (pintype "passive"))
      (node (ref "R62") (pin "1") (pinfunction "1_1") (pintype "passive"))
      (node (ref "R65") (pin "2") (pinfunction "2_2") (pintype "passive"))
    )
    (net (code "125") (name "Net-(POWER-PadC)") (class "Default")
      (node (ref "POWER") (pin "C") (pinfunction "C_C") (pintype "passive"))
      (node (ref "R67") (pin "2") (pinfunction "2_2") (pintype "passive"))
    )
    (net (code "126") (name "Net-(U1-AREFAD1)") (class "Default")
      (node (ref "C39") (pin "1") (pinfunction "1_1") (pintype "passive"))
      (node (ref "U1") (pin "59") (pinfunction "AREFAD1_59") (pintype "passive"))
    )
    (net (code "127") (name "Net-(U1-VCOMDA)") (class "Default")
      (node (ref "C41") (pin "1") (pinfunction "1_1") (pintype "passive"))
      (node (ref "U1") (pin "15") (pinfunction "VCOMDA_15") (pintype "passive"))
    )
    (net (code "128") (name "Net-(U1-VREFAD2)") (class "Default")
      (node (ref "C40") (pin "1") (pinfunction "1_1") (pintype "passive"))
      (node (ref "U1") (pin "60") (pinfunction "VREFAD2_60") (pintype "passive"))
    )
    (net (code "129") (name "Net-(U6-CAP+)") (class "Default")
      (node (ref "C49") (pin "1") (pinfunction "1_1") (pintype "passive"))
      (node (ref "U6") (pin "2") (pinfunction "CAP+_2") (pintype "input"))
    )
    (net (code "130") (name "Net-(U6-CAP-)") (class "Default")
      (node (ref "C49") (pin "2") (pinfunction "2_2") (pintype "passive"))
      (node (ref "U6") (pin "4") (pinfunction "CAP-_4") (pintype "input"))
    )
    (net (code "131") (name "unconnected-(CON1A-1-Pad3-1)") (class "Default")
      (node (ref "CON1") (pin "3-1") (pinfunction "1_3-1") (pintype "passive"))
    )
    (net (code "132") (name "unconnected-(CON1A-3-Pad3-3)") (class "Default")
      (node (ref "CON1") (pin "3-3") (pinfunction "3_3-3") (pintype "passive"))
    )
    (net (code "133") (name "unconnected-(CON1A-5-Pad3-5)") (class "Default")
      (node (ref "CON1") (pin "3-5") (pinfunction "5_3-5") (pintype "passive"))
    )
    (net (code "134") (name "unconnected-(CON1A-6-Pad3-6)") (class "Default")
      (node (ref "CON1") (pin "3-6") (pinfunction "6_3-6") (pintype "passive"))
    )
    (net (code "135") (name "unconnected-(CON1A-7-Pad3-7)") (class "Default")
      (node (ref "CON1") (pin "3-7") (pinfunction "7_3-7") (pintype "passive"))
    )
    (net (code "136") (name "unconnected-(CON1A-8-Pad3-8)") (class "Default")
      (node (ref "CON1") (pin "3-8") (pinfunction "8_3-8") (pintype "passive"))
    )
    (net (code "137") (name "unconnected-(CON1A-9-Pad3-9)") (class "Default")
      (node (ref "CON1") (pin "3-9") (pinfunction "9_3-9") (pintype "passive"))
    )
    (net (code "138") (name "unconnected-(CON1A-11-Pad3-11)") (class "Default")
      (node (ref "CON1") (pin "3-11") (pinfunction "11_3-11") (pintype "passive"))
    )
    (net (code "139") (name "unconnected-(CON1A-13-Pad3-13)") (class "Default")
      (node (ref "CON1") (pin "3-13") (pinfunction "13_3-13") (pintype "passive"))
    )
    (net (code "140") (name "unconnected-(CON1A-15-Pad3-15)") (class "Default")
      (node (ref "CON1") (pin "3-15") (pinfunction "15_3-15") (pintype "passive"))
    )
    (net (code "141") (name "unconnected-(CON1A-17-Pad3-17)") (class "Default")
      (node (ref "CON1") (pin "3-17") (pinfunction "17_3-17") (pintype "passive"))
    )
    (net (code "142") (name "unconnected-(CON1A-19-Pad3-19)") (class "Default")
      (node (ref "CON1") (pin "3-19") (pinfunction "19_3-19") (pintype "passive"))
    )
    (net (code "143") (name "unconnected-(CON1A-21-Pad3-21)") (class "Default")
      (node (ref "CON1") (pin "3-21") (pinfunction "21_3-21") (pintype "passive"))
    )
    (net (code "144") (name "unconnected-(CON1A-23-Pad3-23)") (class "Default")
      (node (ref "CON1") (pin "3-23") (pinfunction "23_3-23") (pintype "passive"))
    )
    (net (code "145") (name "unconnected-(CON1A-25-Pad3-25)") (class "Default")
      (node (ref "CON1") (pin "3-25") (pinfunction "25_3-25") (pintype "passive"))
    )
    (net (code "146") (name "unconnected-(CON1A-27-Pad3-27)") (class "Default")
      (node (ref "CON1") (pin "3-27") (pinfunction "27_3-27") (pintype "passive"))
    )
    (net (code "147") (name "unconnected-(CON1A-29-Pad3-29)") (class "Default")
      (node (ref "CON1") (pin "3-29") (pinfunction "29_3-29") (pintype "passive"))
    )
    (net (code "148") (name "unconnected-(CON1A-31-Pad3-31)") (class "Default")
      (node (ref "CON1") (pin "3-31") (pinfunction "31_3-31") (pintype "passive"))
    )
    (net (code "149") (name "unconnected-(CON1A-33-Pad3-33)") (class "Default")
      (node (ref "CON1") (pin "3-33") (pinfunction "33_3-33") (pintype "passive"))
    )
    (net (code "150") (name "unconnected-(CON1A-34-Pad3-34)") (class "Default")
      (node (ref "CON1") (pin "3-34") (pinfunction "34_3-34") (pintype "passive"))
    )
    (net (code "151") (name "unconnected-(CON1A-35-Pad3-35)") (class "Default")
      (node (ref "CON1") (pin "3-35") (pinfunction "35_3-35") (pintype "passive"))
    )
    (net (code "152") (name "unconnected-(CON1A-36-Pad3-36)") (class "Default")
      (node (ref "CON1") (pin "3-36") (pinfunction "36_3-36") (pintype "passive"))
    )
    (net (code "153") (name "unconnected-(CON1A-37-Pad3-37)") (class "Default")
      (node (ref "CON1") (pin "3-37") (pinfunction "37_3-37") (pintype "passive"))
    )
    (net (code "154") (name "unconnected-(CON1A-38-Pad3-38)") (class "Default")
      (node (ref "CON1") (pin "3-38") (pinfunction "38_3-38") (pintype "passive"))
    )
    (net (code "155") (name "unconnected-(CON1A-39-Pad3-39)") (class "Default")
      (node (ref "CON1") (pin "3-39") (pinfunction "39_3-39") (pintype "passive"))
    )
    (net (code "156") (name "unconnected-(CON1A-40-Pad3-40)") (class "Default")
      (node (ref "CON1") (pin "3-40") (pinfunction "40_3-40") (pintype "passive"))
    )
    (net (code "157") (name "unconnected-(CON1B-5-PadD-5)") (class "Default")
      (node (ref "CON1") (pin "D-5") (pinfunction "5_D-5") (pintype "passive"))
    )
    (net (code "158") (name "unconnected-(CON1B-6-PadD-6)") (class "Default")
      (node (ref "CON1") (pin "D-6") (pinfunction "6_D-6") (pintype "passive"))
    )
    (net (code "159") (name "unconnected-(CON1B-7-PadD-7)") (class "Default")
      (node (ref "CON1") (pin "D-7") (pinfunction "7_D-7") (pintype "passive"))
    )
    (net (code "160") (name "unconnected-(CON1B-8-PadD-8)") (class "Default")
      (node (ref "CON1") (pin "D-8") (pinfunction "8_D-8") (pintype "passive"))
    )
    (net (code "161") (name "unconnected-(CON1B-9-PadD-9)") (class "Default")
      (node (ref "CON1") (pin "D-9") (pinfunction "9_D-9") (pintype "passive"))
    )
    (net (code "162") (name "unconnected-(CON1B-10-PadD-10)") (class "Default")
      (node (ref "CON1") (pin "D-10") (pinfunction "10_D-10") (pintype "passive"))
    )
    (net (code "163") (name "unconnected-(CON1B-11-PadD-11)") (class "Default")
      (node (ref "CON1") (pin "D-11") (pinfunction "11_D-11") (pintype "passive"))
    )
    (net (code "164") (name "unconnected-(CON1B-12-PadD-12)") (class "Default")
      (node (ref "CON1") (pin "D-12") (pinfunction "12_D-12") (pintype "passive"))
    )
    (net (code "165") (name "unconnected-(CON1B-13-PadD-13)") (class "Default")
      (node (ref "CON1") (pin "D-13") (pinfunction "13_D-13") (pintype "passive"))
    )
    (net (code "166") (name "unconnected-(CON1B-14-PadD-14)") (class "Default")
      (node (ref "CON1") (pin "D-14") (pinfunction "14_D-14") (pintype "passive"))
    )
    (net (code "167") (name "unconnected-(CON1B-15-PadD-15)") (class "Default")
      (node (ref "CON1") (pin "D-15") (pinfunction "15_D-15") (pintype "passive"))
    )
    (net (code "168") (name "unconnected-(CON1B-16-PadD-16)") (class "Default")
      (node (ref "CON1") (pin "D-16") (pinfunction "16_D-16") (pintype "passive"))
    )
    (net (code "169") (name "unconnected-(CON1B-17-PadD-17)") (class "Default")
      (node (ref "CON1") (pin "D-17") (pinfunction "17_D-17") (pintype "passive"))
    )
    (net (code "170") (name "unconnected-(CON1B-18-PadD-18)") (class "Default")
      (node (ref "CON1") (pin "D-18") (pinfunction "18_D-18") (pintype "passive"))
    )
    (net (code "171") (name "unconnected-(CON1B-19-PadD-19)") (class "Default")
      (node (ref "CON1") (pin "D-19") (pinfunction "19_D-19") (pintype "passive"))
    )
    (net (code "172") (name "unconnected-(CON1B-20-PadD-20)") (class "Default")
      (node (ref "CON1") (pin "D-20") (pinfunction "20_D-20") (pintype "passive"))
    )
    (net (code "173") (name "unconnected-(CON1B-21-PadD-21)") (class "Default")
      (node (ref "CON1") (pin "D-21") (pinfunction "21_D-21") (pintype "passive"))
    )
    (net (code "174") (name "unconnected-(CON1B-22-PadD-22)") (class "Default")
      (node (ref "CON1") (pin "D-22") (pinfunction "22_D-22") (pintype "passive"))
    )
    (net (code "175") (name "unconnected-(CON1B-23-PadD-23)") (class "Default")
      (node (ref "CON1") (pin "D-23") (pinfunction "23_D-23") (pintype "passive"))
    )
    (net (code "176") (name "unconnected-(CON1B-24-PadD-24)") (class "Default")
      (node (ref "CON1") (pin "D-24") (pinfunction "24_D-24") (pintype "passive"))
    )
    (net (code "177") (name "unconnected-(CON1B-25-PadD-25)") (class "Default")
      (node (ref "CON1") (pin "D-25") (pinfunction "25_D-25") (pintype "passive"))
    )
    (net (code "178") (name "unconnected-(CON1B-26-PadD-26)") (class "Default")
      (node (ref "CON1") (pin "D-26") (pinfunction "26_D-26") (pintype "passive"))
    )
    (net (code "179") (name "unconnected-(CON1B-27-PadD-27)") (class "Default")
      (node (ref "CON1") (pin "D-27") (pinfunction "27_D-27") (pintype "passive"))
    )
    (net (code "180") (name "unconnected-(CON1B-28-PadD-28)") (class "Default")
      (node (ref "CON1") (pin "D-28") (pinfunction "28_D-28") (pintype "passive"))
    )
    (net (code "181") (name "unconnected-(CON1B-29-PadD-29)") (class "Default")
      (node (ref "CON1") (pin "D-29") (pinfunction "29_D-29") (pintype "passive"))
    )
    (net (code "182") (name "unconnected-(CON1B-30-PadD-30)") (class "Default")
      (node (ref "CON1") (pin "D-30") (pinfunction "30_D-30") (pintype "passive"))
    )
    (net (code "183") (name "unconnected-(CON1B-31-PadD-31)") (class "Default")
      (node (ref "CON1") (pin "D-31") (pinfunction "31_D-31") (pintype "passive"))
    )
    (net (code "184") (name "unconnected-(CON1B-32-PadD-32)") (class "Default")
      (node (ref "CON1") (pin "D-32") (pinfunction "32_D-32") (pintype "passive"))
    )
    (net (code "185") (name "unconnected-(CON1B-33-PadD-33)") (class "Default")
      (node (ref "CON1") (pin "D-33") (pinfunction "33_D-33") (pintype "passive"))
    )
    (net (code "186") (name "unconnected-(CON1B-34-PadD-34)") (class "Default")
      (node (ref "CON1") (pin "D-34") (pinfunction "34_D-34") (pintype "passive"))
    )
    (net (code "187") (name "unconnected-(CON1B-35-PadD-35)") (class "Default")
      (node (ref "CON1") (pin "D-35") (pinfunction "35_D-35") (pintype "passive"))
    )
    (net (code "188") (name "unconnected-(CON1B-36-PadD-36)") (class "Default")
      (node (ref "CON1") (pin "D-36") (pinfunction "36_D-36") (pintype "passive"))
    )
    (net (code "189") (name "unconnected-(CON1B-37-PadD-37)") (class "Default")
      (node (ref "CON1") (pin "D-37") (pinfunction "37_D-37") (pintype "passive"))
    )
    (net (code "190") (name "unconnected-(CON1B-38-PadD-38)") (class "Default")
      (node (ref "CON1") (pin "D-38") (pinfunction "38_D-38") (pintype "passive"))
    )
    (net (code "191") (name "unconnected-(CON1B-39-PadD-39)") (class "Default")
      (node (ref "CON1") (pin "D-39") (pinfunction "39_D-39") (pintype "passive"))
    )
    (net (code "192") (name "unconnected-(CON1B-40-PadD-40)") (class "Default")
      (node (ref "CON1") (pin "D-40") (pinfunction "40_D-40") (pintype "passive"))
    )
    (net (code "193") (name "unconnected-(U6-LV-Pad6)") (class "Default")
      (node (ref "U6") (pin "6") (pinfunction "LV_6") (pintype "input"))
    )
    (net (code "194") (name "unconnected-(U6-OSC-Pad7)") (class "Default")
      (node (ref "U6") (pin "7") (pinfunction "OSC_7") (pintype "input"))
    )
  )
)
